# F5529LP_node.net
KiCad netlist of a schematic drawn in EAGLE
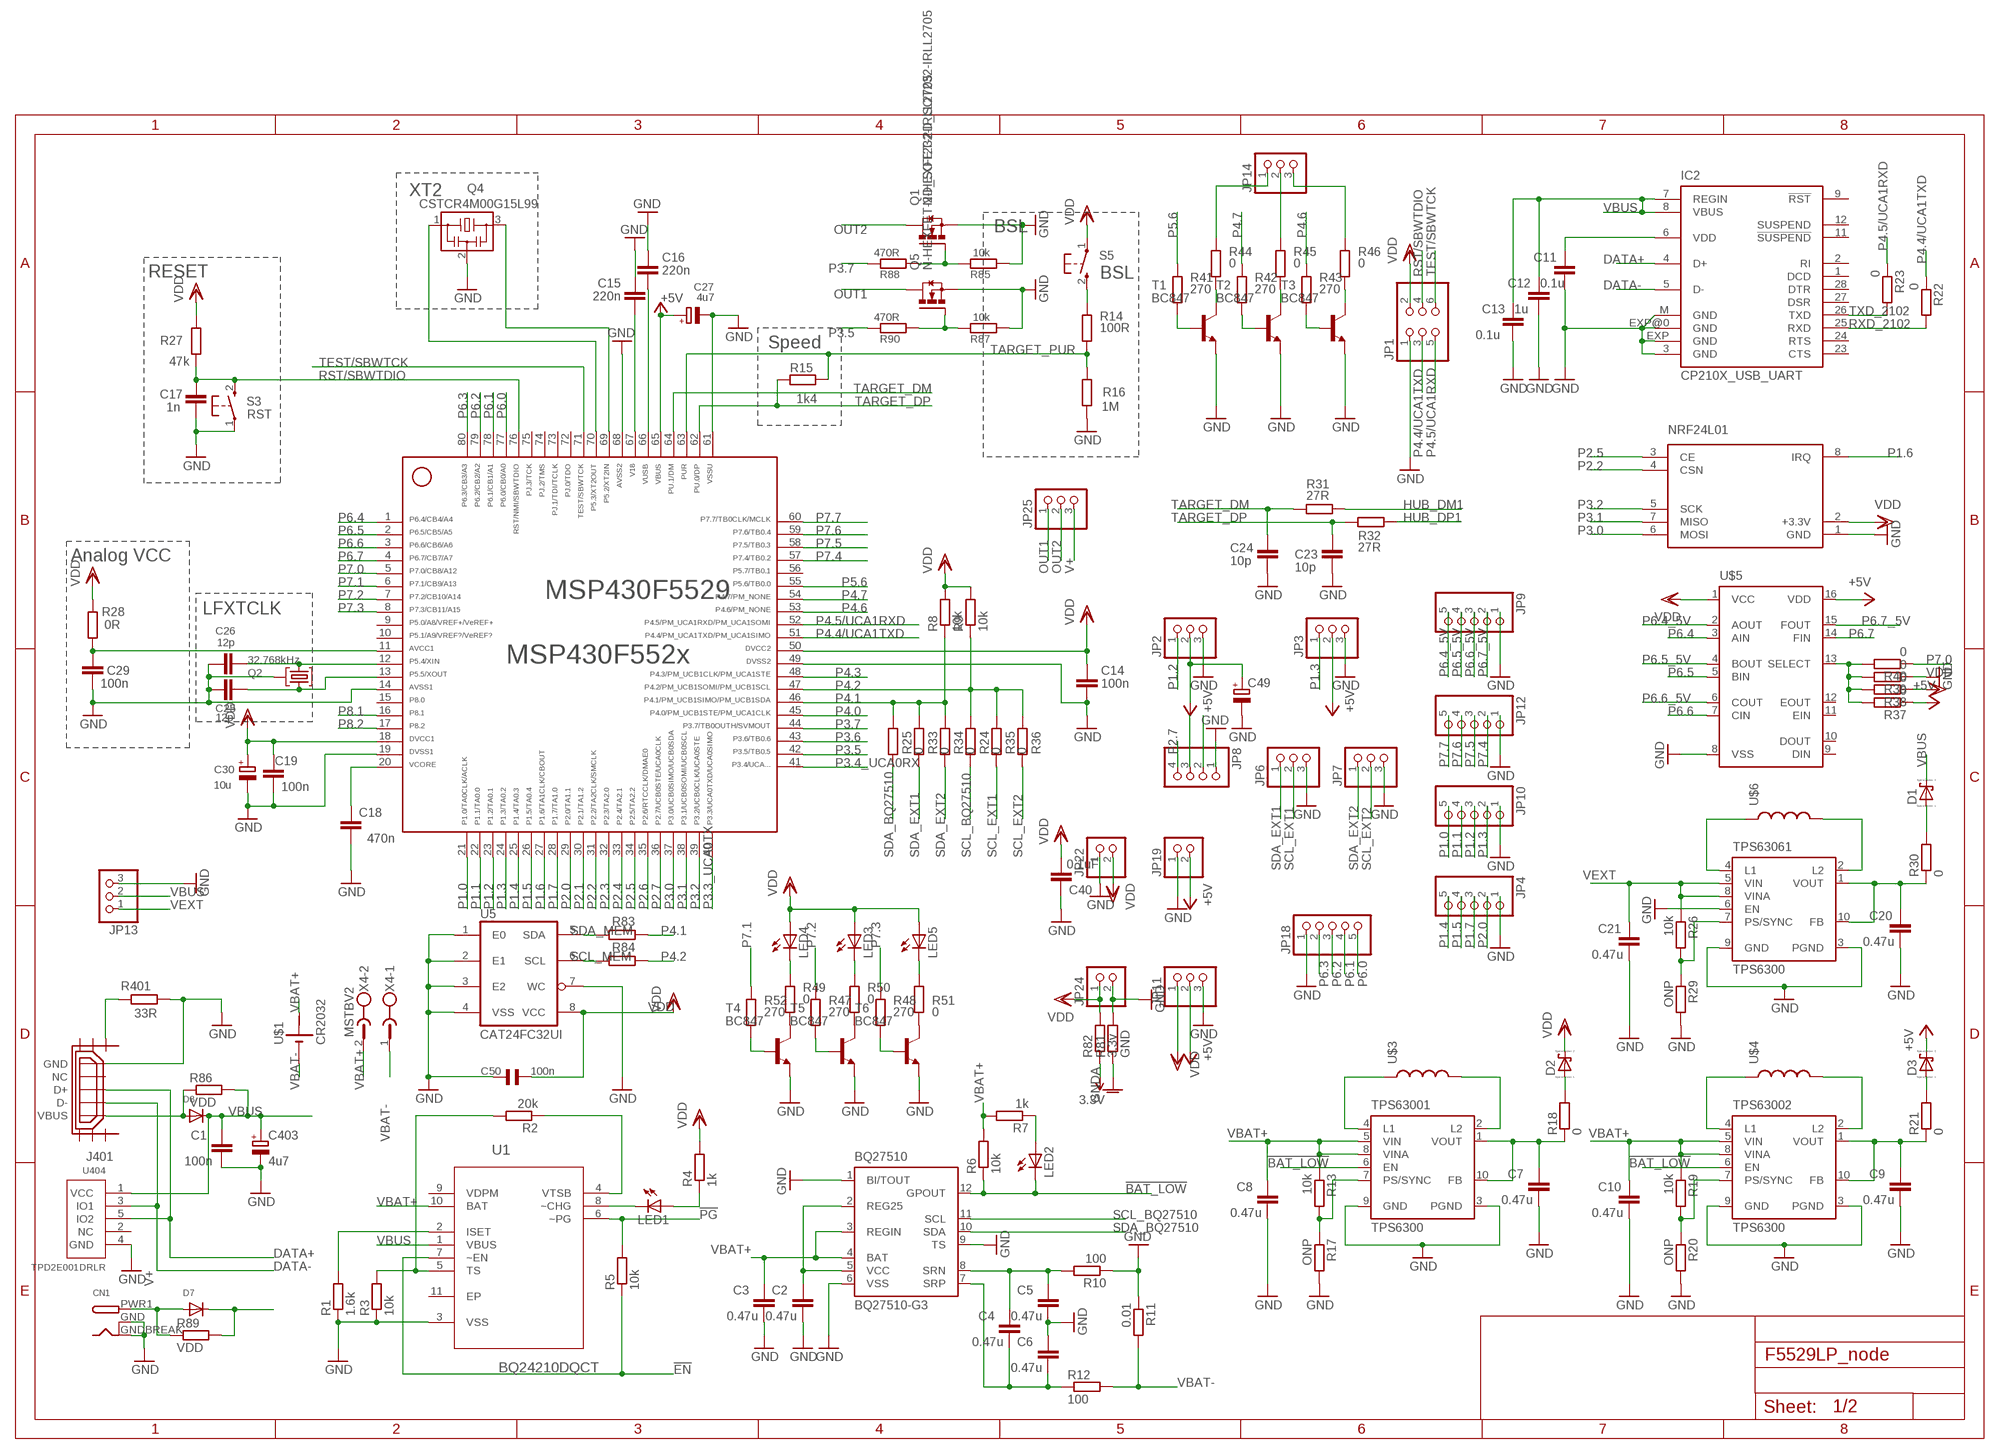
[diagram p0: schematic, sheet 1]
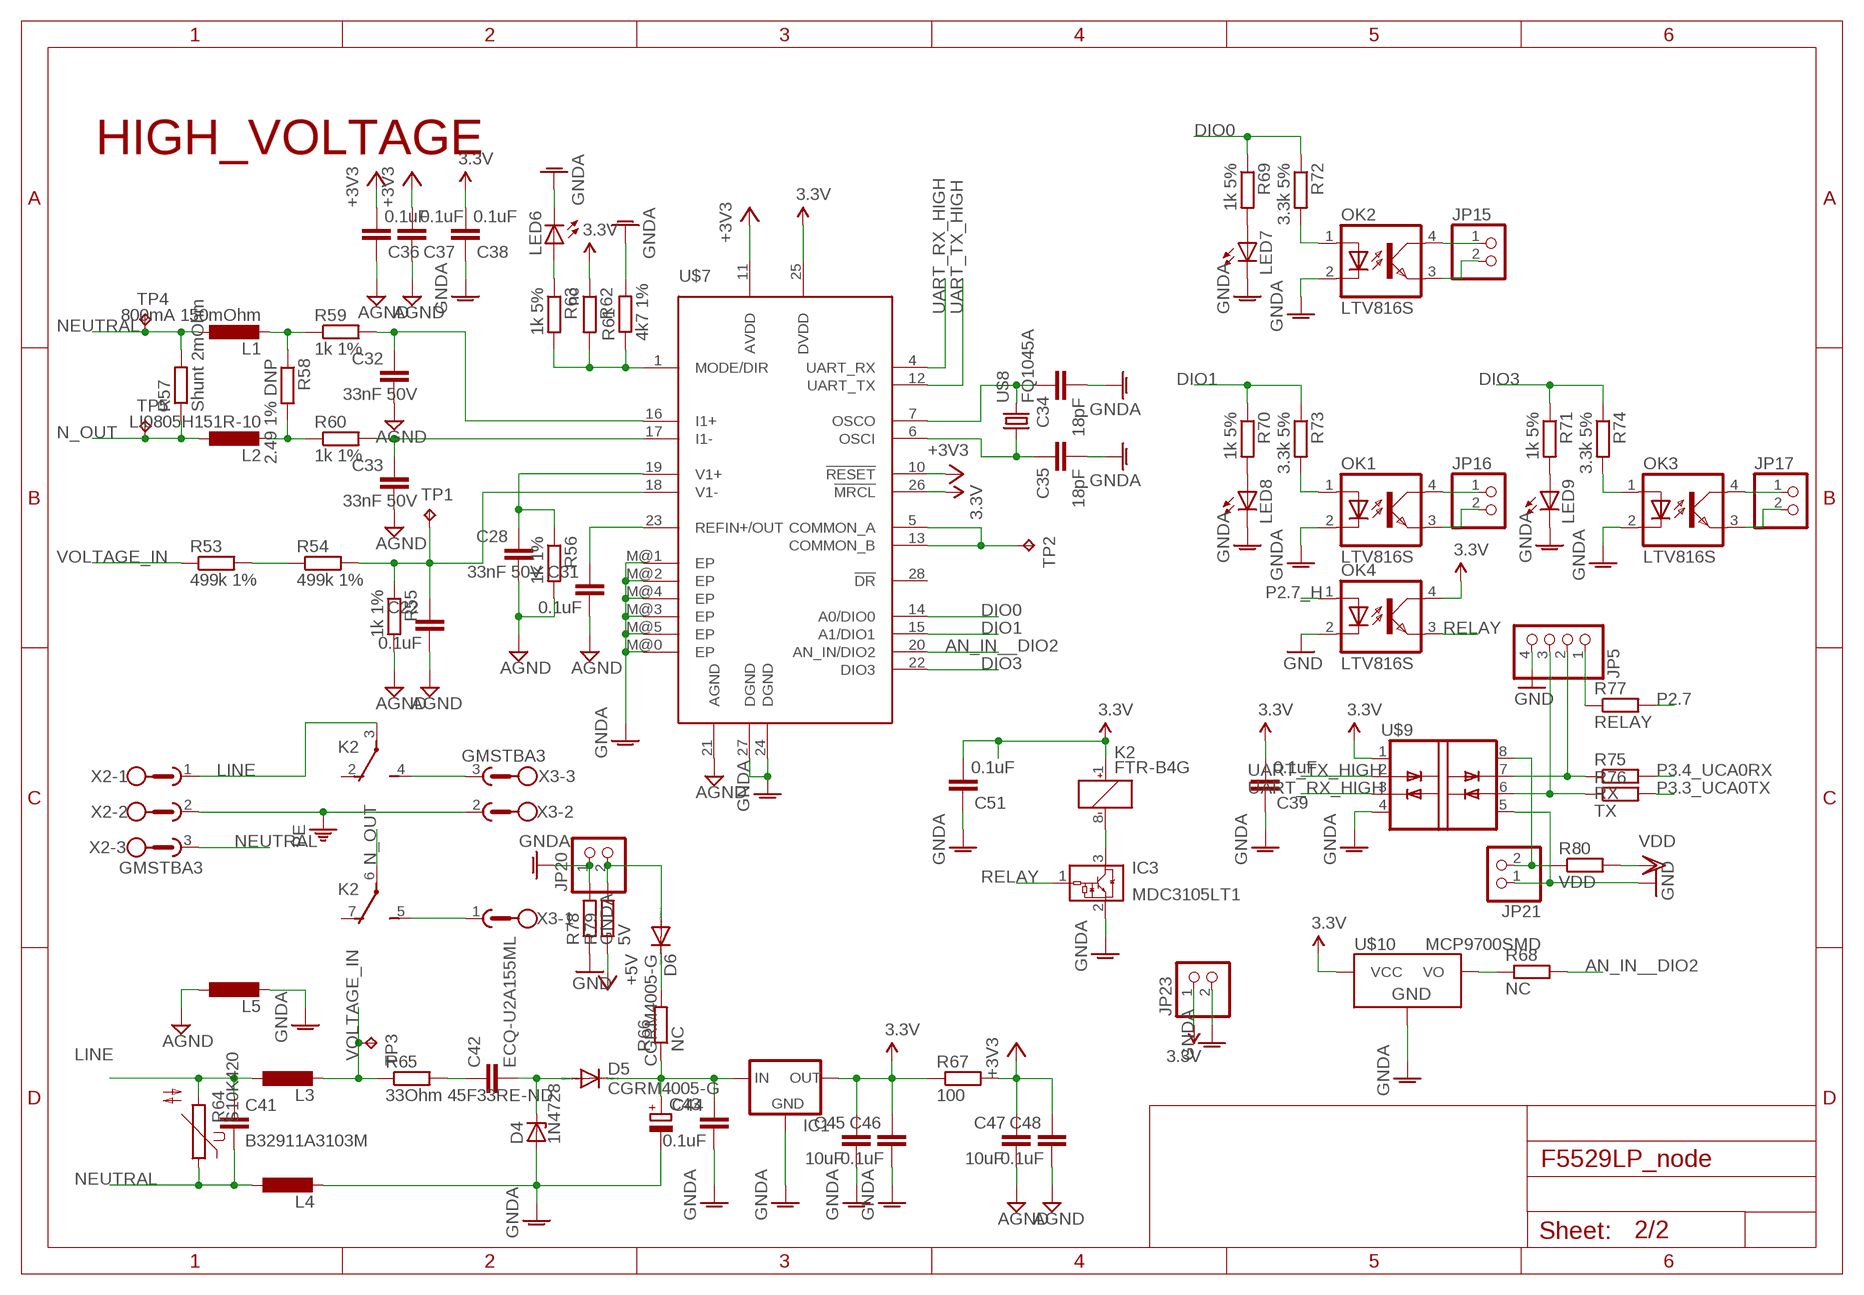
[diagram p1: schematic, sheet 2]

(export (version "E")
  (design (tool "Eeschema 10.0.6"))
  (components
    (comp (ref "BQ27510")
      (value "BQ27510-G3")
      (footprint "eagle-import:DRZ")
      (libsource (lib "eagle-import") (part "BQ27510-G3"))
    )
    (comp (ref "C1")
      (value "100n")
      (footprint "eagle-import:C0603")
      (libsource (lib "eagle-import") (part "C-EUC0603"))
    )
    (comp (ref "C2")
      (value "0.47u")
      (footprint "eagle-import:C0603")
      (libsource (lib "eagle-import") (part "C-EUC0603"))
    )
    (comp (ref "C3")
      (value "0.47u")
      (footprint "eagle-import:C0603")
      (libsource (lib "eagle-import") (part "C-EUC0603"))
    )
    (comp (ref "C4")
      (value "0.47u")
      (footprint "eagle-import:C0603")
      (libsource (lib "eagle-import") (part "C-EUC0603"))
    )
    (comp (ref "C5")
      (value "0.47u")
      (footprint "eagle-import:C0603")
      (libsource (lib "eagle-import") (part "C-EUC0603"))
    )
    (comp (ref "C6")
      (value "0.47u")
      (footprint "eagle-import:C0603")
      (libsource (lib "eagle-import") (part "C-EUC0603"))
    )
    (comp (ref "C7")
      (value "0.47u")
      (footprint "eagle-import:C0603")
      (libsource (lib "eagle-import") (part "C-EUC0603"))
    )
    (comp (ref "C8")
      (value "0.47u")
      (footprint "eagle-import:C0603")
      (libsource (lib "eagle-import") (part "C-EUC0603"))
    )
    (comp (ref "C9")
      (value "0.47u")
      (footprint "eagle-import:C0603")
      (libsource (lib "eagle-import") (part "C-EUC0603"))
    )
    (comp (ref "C10")
      (value "0.47u")
      (footprint "eagle-import:C0603")
      (libsource (lib "eagle-import") (part "C-EUC0603"))
    )
    (comp (ref "C11")
      (value "0.1u")
      (footprint "eagle-import:C0603")
      (libsource (lib "eagle-import") (part "C-EUC0603"))
    )
    (comp (ref "C12")
      (value "1u")
      (footprint "eagle-import:C0603")
      (libsource (lib "eagle-import") (part "C-EUC0603"))
    )
    (comp (ref "C13")
      (value "0.1u")
      (footprint "eagle-import:C0603")
      (libsource (lib "eagle-import") (part "C-EUC0603"))
    )
    (comp (ref "C14")
      (value "100n")
      (footprint "eagle-import:C0603")
      (libsource (lib "eagle-import") (part "C-EUC0603"))
    )
    (comp (ref "C15")
      (value "220n")
      (footprint "eagle-import:C0603")
      (libsource (lib "eagle-import") (part "C-EUC0603"))
    )
    (comp (ref "C16")
      (value "220n")
      (footprint "eagle-import:C0603")
      (libsource (lib "eagle-import") (part "C-EUC0603"))
    )
    (comp (ref "C17")
      (value "1n")
      (footprint "eagle-import:C0603")
      (libsource (lib "eagle-import") (part "C-EUC0603"))
    )
    (comp (ref "C18")
      (value "470n")
      (footprint "eagle-import:C0603")
      (libsource (lib "eagle-import") (part "C-EUC0603"))
    )
    (comp (ref "C19")
      (value "100n")
      (footprint "eagle-import:C0603")
      (libsource (lib "eagle-import") (part "C-EUC0603"))
    )
    (comp (ref "C20")
      (value "0.47u")
      (footprint "eagle-import:C0603")
      (libsource (lib "eagle-import") (part "C-EUC0603"))
    )
    (comp (ref "C21")
      (value "0.47u")
      (footprint "eagle-import:C0603")
      (libsource (lib "eagle-import") (part "C-EUC0603"))
    )
    (comp (ref "C23")
      (value "10p")
      (footprint "eagle-import:C0603")
      (libsource (lib "eagle-import") (part "C-EUC0603"))
    )
    (comp (ref "C24")
      (value "10p")
      (footprint "eagle-import:C0603")
      (libsource (lib "eagle-import") (part "C-EUC0603"))
    )
    (comp (ref "C25")
      (value "12p")
      (footprint "eagle-import:C0603")
      (libsource (lib "eagle-import") (part "C-EUC0603"))
    )
    (comp (ref "C26")
      (value "12p")
      (footprint "eagle-import:C0603")
      (libsource (lib "eagle-import") (part "C-EUC0603"))
    )
    (comp (ref "C27")
      (value "4u7")
      (footprint "eagle-import:A_3216-18R")
      (libsource (lib "eagle-import") (part "CPOL-EUA/3216-18R"))
    )
    (comp (ref "C29")
      (value "100n")
      (footprint "eagle-import:C0603")
      (libsource (lib "eagle-import") (part "C-EUC0603"))
    )
    (comp (ref "C30")
      (value "10u")
      (footprint "eagle-import:A_3216-18R")
      (libsource (lib "eagle-import") (part "CPOL-EUA/3216-18R"))
    )
    (comp (ref "C40")
      (value "0.1uF")
      (footprint "eagle-import:C0603")
      (libsource (lib "eagle-import") (part "C-EUC0603"))
    )
    (comp (ref "C49")
      (value "CPOL-EUF")
      (footprint "eagle-import:PANASONIC_F")
      (libsource (lib "eagle-import") (part "resistor_CPOL-EUF"))
    )
    (comp (ref "C50")
      (value "100n")
      (footprint "eagle-import:0402")
      (libsource (lib "eagle-import") (part "C_SMD0402"))
    )
    (comp (ref "C403")
      (value "4u7")
      (footprint "eagle-import:A_3216-18R")
      (libsource (lib "eagle-import") (part "CPOL-EUA/3216-18R"))
    )
    (comp (ref "CN1")
      (value "DCBARRELSMT")
      (footprint "eagle-import:DCJACK_2MM_SMT")
      (libsource (lib "eagle-import") (part "DCBARRELSMT"))
    )
    (comp (ref "D1")
      (value "SCHOTTKY-DIODE")
      (footprint "eagle-import:DIODE_SMB")
      (libsource (lib "eagle-import") (part "SCHOTTKY-DIODE"))
    )
    (comp (ref "D2")
      (value "SCHOTTKY-DIODE")
      (footprint "eagle-import:DIODE_SMB")
      (libsource (lib "eagle-import") (part "SCHOTTKY-DIODE"))
    )
    (comp (ref "D3")
      (value "SCHOTTKY-DIODE")
      (footprint "eagle-import:DIODE_SMB")
      (libsource (lib "eagle-import") (part "SCHOTTKY-DIODE"))
    )
    (comp (ref "D7")
      (value "DIODESOT23_REFLOW")
      (footprint "eagle-import:SOT23-R")
      (libsource (lib "eagle-import") (part "DIODESOT23_REFLOW"))
    )
    (comp (ref "D8")
      (value "DIODESOT23_REFLOW")
      (footprint "eagle-import:SOT23-R")
      (libsource (lib "eagle-import") (part "DIODESOT23_REFLOW"))
    )
    (comp (ref "IC2")
      (value "CP210X_USB_UART")
      (footprint "eagle-import:MLP28")
      (libsource (lib "eagle-import") (part "CP210X_USB_UART"))
    )
    (comp (ref "J401")
      (value "USB_MICRO_FLIPPED")
      (footprint "eagle-import:HIROSE-ZX62R-B-5P")
      (libsource (lib "eagle-import") (part "USB_MICRO_FLIPPED"))
    )
    (comp (ref "JP1")
      (value "PINHD-2X3")
      (footprint "eagle-import:2X03")
      (libsource (lib "eagle-import") (part "PINHD-2X3"))
    )
    (comp (ref "JP2")
      (value "PINHD-1X3")
      (footprint "eagle-import:1X03")
      (libsource (lib "eagle-import") (part "PINHD-1X3"))
    )
    (comp (ref "JP3")
      (value "PINHD-1X3")
      (footprint "eagle-import:1X03")
      (libsource (lib "eagle-import") (part "PINHD-1X3"))
    )
    (comp (ref "JP4")
      (value "PINHD-1X5_2.00")
      (footprint "eagle-import:1X05M")
      (libsource (lib "eagle-import") (part "PINHD-1X5_2.00"))
    )
    (comp (ref "JP6")
      (value "PINHD-1X3_2.00")
      (footprint "eagle-import:1X03M")
      (libsource (lib "eagle-import") (part "PINHD-1X3_2.00"))
    )
    (comp (ref "JP7")
      (value "PINHD-1X3_2.00")
      (footprint "eagle-import:1X03M")
      (libsource (lib "eagle-import") (part "PINHD-1X3_2.00"))
    )
    (comp (ref "JP8")
      (value "PINHD-1X4_2.00")
      (footprint "eagle-import:1X04M")
      (libsource (lib "eagle-import") (part "PINHD-1X4_2.00"))
    )
    (comp (ref "JP9")
      (value "PINHD-1X5_2.00")
      (footprint "eagle-import:1X05M")
      (libsource (lib "eagle-import") (part "PINHD-1X5_2.00"))
    )
    (comp (ref "JP10")
      (value "PINHD-1X5_2.00")
      (footprint "eagle-import:1X05M")
      (libsource (lib "eagle-import") (part "PINHD-1X5_2.00"))
    )
    (comp (ref "JP11")
      (value "PINHD-1X3_2.00")
      (footprint "eagle-import:1X03M")
      (libsource (lib "eagle-import") (part "PINHD-1X3_2.00"))
    )
    (comp (ref "JP12")
      (value "PINHD-1X5_2.00")
      (footprint "eagle-import:1X05M")
      (libsource (lib "eagle-import") (part "PINHD-1X5_2.00"))
    )
    (comp (ref "JP13")
      (value "PINHD-1X3_2.00")
      (footprint "eagle-import:1X03M")
      (libsource (lib "eagle-import") (part "PINHD-1X3_2.00"))
    )
    (comp (ref "JP14")
      (value "PINHD-1X3_2.00")
      (footprint "eagle-import:1X03M")
      (libsource (lib "eagle-import") (part "PINHD-1X3_2.00"))
    )
    (comp (ref "JP18")
      (value "PINHD-1X5_2.00")
      (footprint "eagle-import:1X05M")
      (libsource (lib "eagle-import") (part "PINHD-1X5_2.00"))
    )
    (comp (ref "JP19")
      (value "PINHD-1X2_2.00")
      (footprint "eagle-import:1X02M")
      (libsource (lib "eagle-import") (part "PINHD-1X2_2.00"))
    )
    (comp (ref "JP22")
      (value "PINHD-1X2_2.00")
      (footprint "eagle-import:1X02M")
      (libsource (lib "eagle-import") (part "PINHD-1X2_2.00"))
    )
    (comp (ref "JP24")
      (value "PINHD-1X2_2.00")
      (footprint "eagle-import:1X02M")
      (libsource (lib "eagle-import") (part "PINHD-1X2_2.00"))
    )
    (comp (ref "JP25")
      (value "PINHD-1X3")
      (footprint "eagle-import:1X03")
      (libsource (lib "eagle-import") (part "PINHD-1X3"))
    )
    (comp (ref "LED1")
      (value "LEDSML0805")
      (footprint "eagle-import:SML0805")
      (libsource (lib "eagle-import") (part "LEDSML0805"))
    )
    (comp (ref "LED2")
      (value "LEDSML0805")
      (footprint "eagle-import:SML0805")
      (libsource (lib "eagle-import") (part "LEDSML0805"))
    )
    (comp (ref "LED3")
      (value "LEDSML0805")
      (footprint "eagle-import:SML0805")
      (libsource (lib "eagle-import") (part "LEDSML0805"))
    )
    (comp (ref "LED4")
      (value "LEDSML0805")
      (footprint "eagle-import:SML0805")
      (libsource (lib "eagle-import") (part "LEDSML0805"))
    )
    (comp (ref "LED5")
      (value "LEDSML0805")
      (footprint "eagle-import:SML0805")
      (libsource (lib "eagle-import") (part "LEDSML0805"))
    )
    (comp (ref "MSP430F5529")
      (value "MSP430F5529IPNR")
      (footprint "eagle-import:PN80")
      (libsource (lib "eagle-import") (part "F552X---PN80"))
    )
    (comp (ref "NRF24L01")
      (value "NRF24L01HP")
      (footprint "eagle-import:NRF24L01_HP")
      (libsource (lib "eagle-import") (part "NRF24L01HP"))
    )
    (comp (ref "Q1")
      (value "N-HEXFET-2D_SOT232-IRLL2705")
      (footprint "eagle-import:SOT223")
      (libsource (lib "eagle-import") (part "N-HEXFET-2D_?-SOT232IRLL2705"))
    )
    (comp (ref "Q2")
      (value "32.768kHz")
      (footprint "eagle-import:MS3V-T1R")
      (libsource (lib "eagle-import") (part "MS3V-T1R"))
    )
    (comp (ref "Q4")
      (value "CSTCR4M00G15L99")
      (footprint "eagle-import:MURATA-FILTER_CSTCR")
      (fields (field (name "MPN") "CSTCR6M00G53-R0"))
      (libsource (lib "eagle-import") (part "MURATA-FILTER_CSTCR6M00G53Z"))
    )
    (comp (ref "Q5")
      (value "N-HEXFET-2D_SOT232-IRLL2705")
      (footprint "eagle-import:SOT223")
      (libsource (lib "eagle-import") (part "N-HEXFET-2D_?-SOT232IRLL2705"))
    )
    (comp (ref "R1")
      (value "1.6k")
      (footprint "eagle-import:R0603")
      (libsource (lib "eagle-import") (part "resistor_R-EU_R0603"))
    )
    (comp (ref "R2")
      (value "20k")
      (footprint "eagle-import:R0603")
      (libsource (lib "eagle-import") (part "resistor_R-EU_R0603"))
    )
    (comp (ref "R3")
      (value "10k")
      (footprint "eagle-import:R0603")
      (libsource (lib "eagle-import") (part "resistor_R-EU_R0603"))
    )
    (comp (ref "R4")
      (value "1k")
      (footprint "eagle-import:R0603")
      (libsource (lib "eagle-import") (part "resistor_R-EU_R0603"))
    )
    (comp (ref "R5")
      (value "10k")
      (footprint "eagle-import:R0603")
      (libsource (lib "eagle-import") (part "resistor_R-EU_R0603"))
    )
    (comp (ref "R6")
      (value "10k")
      (footprint "eagle-import:R0603")
      (libsource (lib "eagle-import") (part "resistor_R-EU_R0603"))
    )
    (comp (ref "R7")
      (value "1k")
      (footprint "eagle-import:R0603")
      (libsource (lib "eagle-import") (part "resistor_R-EU_R0603"))
    )
    (comp (ref "R8")
      (value "10k")
      (footprint "eagle-import:R0603")
      (libsource (lib "eagle-import") (part "resistor_R-EU_R0603"))
    )
    (comp (ref "R9")
      (value "10k")
      (footprint "eagle-import:R0603")
      (libsource (lib "eagle-import") (part "resistor_R-EU_R0603"))
    )
    (comp (ref "R10")
      (value "100")
      (footprint "eagle-import:R0603")
      (libsource (lib "eagle-import") (part "resistor_R-EU_R0603"))
    )
    (comp (ref "R11")
      (value "0.01")
      (footprint "eagle-import:R0603")
      (libsource (lib "eagle-import") (part "resistor_R-EU_R0603"))
    )
    (comp (ref "R12")
      (value "100")
      (footprint "eagle-import:R0603")
      (libsource (lib "eagle-import") (part "resistor_R-EU_R0603"))
    )
    (comp (ref "R13")
      (value "10k")
      (footprint "eagle-import:R0603")
      (libsource (lib "eagle-import") (part "resistor_R-EU_R0603"))
    )
    (comp (ref "R14")
      (value "100R")
      (footprint "eagle-import:R0603")
      (libsource (lib "eagle-import") (part "R-EU_R0603"))
    )
    (comp (ref "R15")
      (value "1k4")
      (footprint "eagle-import:R0603")
      (libsource (lib "eagle-import") (part "R-EU_R0603"))
    )
    (comp (ref "R16")
      (value "1M")
      (footprint "eagle-import:R0603")
      (libsource (lib "eagle-import") (part "R-EU_R0603"))
    )
    (comp (ref "R17")
      (value "ONP")
      (footprint "eagle-import:R0603")
      (libsource (lib "eagle-import") (part "resistor_R-EU_R0603"))
    )
    (comp (ref "R18")
      (value "0")
      (footprint "eagle-import:R0603")
      (libsource (lib "eagle-import") (part "resistor_R-EU_R0603"))
    )
    (comp (ref "R19")
      (value "10k")
      (footprint "eagle-import:R0603")
      (libsource (lib "eagle-import") (part "resistor_R-EU_R0603"))
    )
    (comp (ref "R20")
      (value "ONP")
      (footprint "eagle-import:R0603")
      (libsource (lib "eagle-import") (part "resistor_R-EU_R0603"))
    )
    (comp (ref "R21")
      (value "0")
      (footprint "eagle-import:R0603")
      (libsource (lib "eagle-import") (part "resistor_R-EU_R0603"))
    )
    (comp (ref "R22")
      (value "0")
      (footprint "eagle-import:R0603")
      (libsource (lib "eagle-import") (part "resistor_R-EU_R0603"))
    )
    (comp (ref "R23")
      (value "0")
      (footprint "eagle-import:R0603")
      (libsource (lib "eagle-import") (part "resistor_R-EU_R0603"))
    )
    (comp (ref "R24")
      (value "0")
      (footprint "eagle-import:R0201")
      (libsource (lib "eagle-import") (part "R-EU_R0201"))
    )
    (comp (ref "R25")
      (value "0")
      (footprint "eagle-import:R0201")
      (libsource (lib "eagle-import") (part "R-EU_R0201"))
    )
    (comp (ref "R26")
      (value "10k")
      (footprint "eagle-import:R0603")
      (libsource (lib "eagle-import") (part "resistor_R-EU_R0603"))
    )
    (comp (ref "R27")
      (value "47k")
      (footprint "eagle-import:R0603")
      (libsource (lib "eagle-import") (part "R-EU_R0603"))
    )
    (comp (ref "R28")
      (value "0R")
      (footprint "eagle-import:R0603")
      (libsource (lib "eagle-import") (part "R-EU_R0603"))
    )
    (comp (ref "R29")
      (value "ONP")
      (footprint "eagle-import:R0603")
      (libsource (lib "eagle-import") (part "resistor_R-EU_R0603"))
    )
    (comp (ref "R30")
      (value "0")
      (footprint "eagle-import:R0603")
      (libsource (lib "eagle-import") (part "resistor_R-EU_R0603"))
    )
    (comp (ref "R31")
      (value "27R")
      (footprint "eagle-import:R0603")
      (libsource (lib "eagle-import") (part "R-EU_R0603"))
    )
    (comp (ref "R32")
      (value "27R")
      (footprint "eagle-import:R0603")
      (libsource (lib "eagle-import") (part "R-EU_R0603"))
    )
    (comp (ref "R33")
      (value "0")
      (footprint "eagle-import:R0201")
      (libsource (lib "eagle-import") (part "R-EU_R0201"))
    )
    (comp (ref "R34")
      (value "0")
      (footprint "eagle-import:R0201")
      (libsource (lib "eagle-import") (part "R-EU_R0201"))
    )
    (comp (ref "R35")
      (value "0")
      (footprint "eagle-import:R0201")
      (libsource (lib "eagle-import") (part "R-EU_R0201"))
    )
    (comp (ref "R36")
      (value "0")
      (footprint "eagle-import:R0201")
      (libsource (lib "eagle-import") (part "R-EU_R0201"))
    )
    (comp (ref "R37")
      (value "0")
      (footprint "eagle-import:R0603")
      (libsource (lib "eagle-import") (part "resistor_R-EU_R0603"))
    )
    (comp (ref "R38")
      (value "0")
      (footprint "eagle-import:R0603")
      (libsource (lib "eagle-import") (part "resistor_R-EU_R0603"))
    )
    (comp (ref "R39")
      (value "0")
      (footprint "eagle-import:R0603")
      (libsource (lib "eagle-import") (part "resistor_R-EU_R0603"))
    )
    (comp (ref "R40")
      (value "0")
      (footprint "eagle-import:R0603")
      (libsource (lib "eagle-import") (part "resistor_R-EU_R0603"))
    )
    (comp (ref "R41")
      (value "270")
      (footprint "eagle-import:R0603")
      (libsource (lib "eagle-import") (part "R-EU_R0603"))
    )
    (comp (ref "R42")
      (value "270")
      (footprint "eagle-import:R0603")
      (libsource (lib "eagle-import") (part "R-EU_R0603"))
    )
    (comp (ref "R43")
      (value "270")
      (footprint "eagle-import:R0603")
      (libsource (lib "eagle-import") (part "R-EU_R0603"))
    )
    (comp (ref "R44")
      (value "0")
      (footprint "eagle-import:R0603")
      (libsource (lib "eagle-import") (part "R-EU_R0603"))
    )
    (comp (ref "R45")
      (value "0")
      (footprint "eagle-import:R0603")
      (libsource (lib "eagle-import") (part "R-EU_R0603"))
    )
    (comp (ref "R46")
      (value "0")
      (footprint "eagle-import:R0603")
      (libsource (lib "eagle-import") (part "R-EU_R0603"))
    )
    (comp (ref "R47")
      (value "270")
      (footprint "eagle-import:R0603")
      (libsource (lib "eagle-import") (part "R-EU_R0603"))
    )
    (comp (ref "R48")
      (value "270")
      (footprint "eagle-import:R0603")
      (libsource (lib "eagle-import") (part "R-EU_R0603"))
    )
    (comp (ref "R49")
      (value "0")
      (footprint "eagle-import:R0603")
      (libsource (lib "eagle-import") (part "R-EU_R0603"))
    )
    (comp (ref "R50")
      (value "0")
      (footprint "eagle-import:R0603")
      (libsource (lib "eagle-import") (part "R-EU_R0603"))
    )
    (comp (ref "R51")
      (value "0")
      (footprint "eagle-import:R0603")
      (libsource (lib "eagle-import") (part "R-EU_R0603"))
    )
    (comp (ref "R52")
      (value "270")
      (footprint "eagle-import:R0603")
      (libsource (lib "eagle-import") (part "R-EU_R0603"))
    )
    (comp (ref "R81")
      (value "GND")
      (footprint "eagle-import:R0402")
      (libsource (lib "eagle-import") (part "resistor_R-EU_R0402"))
    )
    (comp (ref "R82")
      (value "3.3v")
      (footprint "eagle-import:R0402")
      (libsource (lib "eagle-import") (part "resistor_R-EU_R0402"))
    )
    (comp (ref "R83")
      (value "0")
      (footprint "eagle-import:R0201")
      (libsource (lib "eagle-import") (part "R-EU_R0201"))
    )
    (comp (ref "R84")
      (value "0")
      (footprint "eagle-import:R0201")
      (libsource (lib "eagle-import") (part "R-EU_R0201"))
    )
    (comp (ref "R85")
      (value "10k")
      (footprint "eagle-import:0603")
      (libsource (lib "eagle-import") (part "R_SMDR0603"))
    )
    (comp (ref "R86")
      (value "VDD")
      (footprint "eagle-import:R0201")
      (libsource (lib "eagle-import") (part "resistor_R-EU_R0201"))
    )
    (comp (ref "R87")
      (value "10k")
      (footprint "eagle-import:0603")
      (libsource (lib "eagle-import") (part "R_SMDR0603"))
    )
    (comp (ref "R88")
      (value "470R")
      (footprint "eagle-import:0603")
      (libsource (lib "eagle-import") (part "R_SMDR0603"))
    )
    (comp (ref "R89")
      (value "VDD")
      (footprint "eagle-import:R0201")
      (libsource (lib "eagle-import") (part "resistor_R-EU_R0201"))
    )
    (comp (ref "R90")
      (value "470R")
      (footprint "eagle-import:0603")
      (libsource (lib "eagle-import") (part "R_SMDR0603"))
    )
    (comp (ref "R401")
      (value "33R")
      (footprint "eagle-import:R0603")
      (libsource (lib "eagle-import") (part "R-EU_R0603"))
    )
    (comp (ref "S3")
      (value "RST")
      (footprint "eagle-import:PBTH")
      (libsource (lib "eagle-import") (part "PB"))
    )
    (comp (ref "S5")
      (value "BSL")
      (footprint "eagle-import:PBTH")
      (libsource (lib "eagle-import") (part "PB"))
    )
    (comp (ref "T1")
      (value "BC847")
      (footprint "eagle-import:SOT23")
      (libsource (lib "eagle-import") (part "BC847"))
    )
    (comp (ref "T2")
      (value "BC847")
      (footprint "eagle-import:SOT23")
      (libsource (lib "eagle-import") (part "BC847"))
    )
    (comp (ref "T3")
      (value "BC847")
      (footprint "eagle-import:SOT23")
      (libsource (lib "eagle-import") (part "BC847"))
    )
    (comp (ref "T4")
      (value "BC847")
      (footprint "eagle-import:SOT23")
      (libsource (lib "eagle-import") (part "BC847"))
    )
    (comp (ref "T5")
      (value "BC847")
      (footprint "eagle-import:SOT23")
      (libsource (lib "eagle-import") (part "BC847"))
    )
    (comp (ref "T6")
      (value "BC847")
      (footprint "eagle-import:SOT23")
      (libsource (lib "eagle-import") (part "BC847"))
    )
    (comp (ref "TPS63001")
      (value "TPS6300")
      (footprint "eagle-import:DRC-S-PVSON-N10")
      (fields (field (name "MPN") "TPS63000DRCTG4"))
      (libsource (lib "eagle-import") (part "TPS6300"))
    )
    (comp (ref "TPS63002")
      (value "TPS6300")
      (footprint "eagle-import:DRC-S-PVSON-N10")
      (fields (field (name "MPN") "TPS63000DRCTG4"))
      (libsource (lib "eagle-import") (part "TPS6300"))
    )
    (comp (ref "TPS63061")
      (value "TPS6300")
      (footprint "eagle-import:DRC-S-PVSON-N10")
      (fields (field (name "MPN") "TPS63000DRCTG4"))
      (libsource (lib "eagle-import") (part "TPS6300"))
    )
    (comp (ref "U$1")
      (value "CR2032")
      (footprint "eagle-import:CR2032")
      (libsource (lib "eagle-import") (part "CR2032"))
    )
    (comp (ref "U$3")
      (value "INDUCTOR-B82462G")
      (footprint "eagle-import:B82462G")
      (libsource (lib "eagle-import") (part "INDUCTOR-B82462G"))
    )
    (comp (ref "U$4")
      (value "INDUCTOR-B82462G")
      (footprint "eagle-import:B82462G")
      (libsource (lib "eagle-import") (part "INDUCTOR-B82462G"))
    )
    (comp (ref "U$5")
      (value "CD4504B")
      (footprint "eagle-import:SOIC16")
      (libsource (lib "eagle-import") (part "CD4504B"))
    )
    (comp (ref "U$6")
      (value "INDUCTOR-B82462G")
      (footprint "eagle-import:B82462G")
      (libsource (lib "eagle-import") (part "INDUCTOR-B82462G"))
    )
    (comp (ref "U1")
      (value "BQ24210DQCT")
      (footprint "eagle-import:SON50P200X300X80-11N")
      (libsource (lib "eagle-import") (part "BQ24210DQCT"))
    )
    (comp (ref "U5")
      (value "CAT24FC32UI")
      (footprint "eagle-import:TSSOP8")
      (libsource (lib "eagle-import") (part "M24XXX"))
    )
    (comp (ref "U404")
      (value "TPD2E001DRLR")
      (footprint "eagle-import:TPD2E001-DRL")
      (libsource (lib "eagle-import") (part "TPD2E001"))
    )
    (comp (ref "X4")
      (value "MSTBV2")
      (footprint "eagle-import:MSTBV2")
      (fields (field (name "MPN") "MSTBV 2,5/2-GF-5.08"))
      (libsource (lib "eagle-import") (part "MSTBV2"))
    )
    (comp (ref "C22")
      (value "0.1uF")
      (footprint "eagle-import:C0603")
      (libsource (lib "eagle-import") (part "C-EUC0603"))
    )
    (comp (ref "C28")
      (value "33nF 50V")
      (footprint "eagle-import:C0603")
      (libsource (lib "eagle-import") (part "C-EUC0603"))
    )
    (comp (ref "C31")
      (value "0.1uF")
      (footprint "eagle-import:C0603")
      (libsource (lib "eagle-import") (part "C-EUC0603"))
    )
    (comp (ref "C32")
      (value "33nF 50V")
      (footprint "eagle-import:C0603")
      (libsource (lib "eagle-import") (part "C-EUC0603"))
    )
    (comp (ref "C33")
      (value "33nF 50V")
      (footprint "eagle-import:C0603")
      (libsource (lib "eagle-import") (part "C-EUC0603"))
    )
    (comp (ref "C34")
      (value "18pF")
      (footprint "eagle-import:C0603")
      (libsource (lib "eagle-import") (part "C-EUC0603"))
    )
    (comp (ref "C35")
      (value "18pF")
      (footprint "eagle-import:C0603")
      (libsource (lib "eagle-import") (part "C-EUC0603"))
    )
    (comp (ref "C36")
      (value "0.1uF")
      (footprint "eagle-import:C0603")
      (libsource (lib "eagle-import") (part "C-EUC0603"))
    )
    (comp (ref "C37")
      (value "0.1uF")
      (footprint "eagle-import:C0603")
      (libsource (lib "eagle-import") (part "C-EUC0603"))
    )
    (comp (ref "C38")
      (value "0.1uF")
      (footprint "eagle-import:C0603")
      (libsource (lib "eagle-import") (part "C-EUC0603"))
    )
    (comp (ref "C39")
      (value "0.1uF")
      (footprint "eagle-import:C0603")
      (libsource (lib "eagle-import") (part "C-EUC0603"))
    )
    (comp (ref "C41")
      (value "B32911A3103M")
      (footprint "eagle-import:C075-042X103")
      (libsource (lib "eagle-import") (part "resistor_C-EU075-042X103"))
    )
    (comp (ref "C42")
      (value "ECQ-U2A155ML")
      (footprint "eagle-import:C275-173X316")
      (libsource (lib "eagle-import") (part "resistor_C-EU275-173X316"))
    )
    (comp (ref "C43")
      (value "CPOL-EUF")
      (footprint "eagle-import:PANASONIC_F")
      (libsource (lib "eagle-import") (part "resistor_CPOL-EUF"))
    )
    (comp (ref "C44")
      (value "0.1uF")
      (footprint "eagle-import:C0603")
      (libsource (lib "eagle-import") (part "C-EUC0603"))
    )
    (comp (ref "C45")
      (value "10uF")
      (footprint "eagle-import:C1206")
      (libsource (lib "eagle-import") (part "C-EUC1206"))
    )
    (comp (ref "C46")
      (value "0.1uF")
      (footprint "eagle-import:C0603")
      (libsource (lib "eagle-import") (part "C-EUC0603"))
    )
    (comp (ref "C47")
      (value "10uF")
      (footprint "eagle-import:C1206")
      (libsource (lib "eagle-import") (part "C-EUC1206"))
    )
    (comp (ref "C48")
      (value "0.1uF")
      (footprint "eagle-import:C0603")
      (libsource (lib "eagle-import") (part "C-EUC0603"))
    )
    (comp (ref "C51")
      (value "0.1uF")
      (footprint "eagle-import:C0805")
      (libsource (lib "eagle-import") (part "C-EUC0805"))
    )
    (comp (ref "D4")
      (value "1N4728")
      (footprint "eagle-import:DO41Z10")
      (libsource (lib "eagle-import") (part "1N4728"))
    )
    (comp (ref "D5")
      (value "CGRM4005-G")
      (footprint "eagle-import:SOD-123_MINI-SMA")
      (libsource (lib "eagle-import") (part "CGRM400-G5"))
    )
    (comp (ref "D6")
      (value "CGRM4005-G")
      (footprint "eagle-import:SOD-123_MINI-SMA")
      (libsource (lib "eagle-import") (part "CGRM400-G5"))
    )
    (comp (ref "IC1")
      (value "LM1117")
      (footprint "eagle-import:SOT223")
      (libsource (lib "eagle-import") (part "LM1117"))
    )
    (comp (ref "IC3")
      (value "MDC3105LT1")
      (footprint "eagle-import:SOT23")
      (fields (field (name "MF") "ON SEMICONDUCTOR"))
      (libsource (lib "eagle-import") (part "MDC3105LT1"))
    )
    (comp (ref "JP5")
      (value "PINHD-1X4_2.00")
      (footprint "eagle-import:1X04M")
      (libsource (lib "eagle-import") (part "PINHD-1X4_2.00"))
    )
    (comp (ref "JP15")
      (value "PINHD-1X2_2.00")
      (footprint "eagle-import:1X02M")
      (libsource (lib "eagle-import") (part "PINHD-1X2_2.00"))
    )
    (comp (ref "JP16")
      (value "PINHD-1X2_2.00")
      (footprint "eagle-import:1X02M")
      (libsource (lib "eagle-import") (part "PINHD-1X2_2.00"))
    )
    (comp (ref "JP17")
      (value "PINHD-1X2_2.00")
      (footprint "eagle-import:1X02M")
      (libsource (lib "eagle-import") (part "PINHD-1X2_2.00"))
    )
    (comp (ref "JP20")
      (value "PINHD-1X2_2.00")
      (footprint "eagle-import:1X02M")
      (libsource (lib "eagle-import") (part "PINHD-1X2_2.00"))
    )
    (comp (ref "JP21")
      (value "PINHD-1X2_2.00")
      (footprint "eagle-import:1X02M")
      (libsource (lib "eagle-import") (part "PINHD-1X2_2.00"))
    )
    (comp (ref "JP23")
      (value "PINHD-1X2_2.00")
      (footprint "eagle-import:1X02M")
      (libsource (lib "eagle-import") (part "PINHD-1X2_2.00"))
    )
    (comp (ref "K2")
      (value "FTR-B4G")
      (footprint "eagle-import:FTR-B4G")
      (libsource (lib "eagle-import") (part "FTR-B4G"))
    )
    (comp (ref "L1")
      (value "800mA 150mOhm")
      (footprint "eagle-import:L2825P")
      (libsource (lib "eagle-import") (part "L-EUL2825P"))
    )
    (comp (ref "L2")
      (value "LI0805H151R-10")
      (footprint "eagle-import:L2825P")
      (libsource (lib "eagle-import") (part "L-EUL2825P"))
    )
    (comp (ref "L3")
      (value "L-EU0207/5V")
      (footprint "eagle-import:0207_5V")
      (libsource (lib "eagle-import") (part "L-EU0207/5V"))
    )
    (comp (ref "L4")
      (value "L-EU0207/5V")
      (footprint "eagle-import:0207_5V")
      (libsource (lib "eagle-import") (part "L-EU0207/5V"))
    )
    (comp (ref "L5")
      (value "L-EUL2825P")
      (footprint "eagle-import:L2825P")
      (libsource (lib "eagle-import") (part "L-EUL2825P"))
    )
    (comp (ref "LED6")
      (value "LEDCHIPLED_0805")
      (footprint "eagle-import:CHIPLED_0805")
      (libsource (lib "eagle-import") (part "LEDCHIPLED_0805"))
    )
    (comp (ref "LED7")
      (value "LEDCHIPLED_0805")
      (footprint "eagle-import:CHIPLED_0805")
      (libsource (lib "eagle-import") (part "LEDCHIPLED_0805"))
    )
    (comp (ref "LED8")
      (value "LEDCHIPLED_0805")
      (footprint "eagle-import:CHIPLED_0805")
      (libsource (lib "eagle-import") (part "LEDCHIPLED_0805"))
    )
    (comp (ref "LED9")
      (value "LEDCHIPLED_0805")
      (footprint "eagle-import:CHIPLED_0805")
      (libsource (lib "eagle-import") (part "LEDCHIPLED_0805"))
    )
    (comp (ref "OK1")
      (value "LTV816S")
      (footprint "eagle-import:SMD4")
      (libsource (lib "eagle-import") (part "LTV816S"))
    )
    (comp (ref "OK2")
      (value "LTV816S")
      (footprint "eagle-import:SMD4")
      (libsource (lib "eagle-import") (part "LTV816S"))
    )
    (comp (ref "OK3")
      (value "LTV816S")
      (footprint "eagle-import:SMD4")
      (libsource (lib "eagle-import") (part "LTV816S"))
    )
    (comp (ref "OK4")
      (value "LTV816S")
      (footprint "eagle-import:SMD4")
      (libsource (lib "eagle-import") (part "LTV816S"))
    )
    (comp (ref "R53")
      (value "499k 1%")
      (footprint "eagle-import:R2010")
      (libsource (lib "eagle-import") (part "resistor_R-EU_R2010"))
    )
    (comp (ref "R54")
      (value "499k 1%")
      (footprint "eagle-import:R2010")
      (libsource (lib "eagle-import") (part "resistor_R-EU_R2010"))
    )
    (comp (ref "R55")
      (value "1k 1%")
      (footprint "eagle-import:R0603")
      (libsource (lib "eagle-import") (part "resistor_R-EU_R0603"))
    )
    (comp (ref "R56")
      (value "1k 1%")
      (footprint "eagle-import:R0603")
      (libsource (lib "eagle-import") (part "resistor_R-EU_R0603"))
    )
    (comp (ref "R57")
      (value "Shunt 2mOhm")
      (footprint "eagle-import:R2512")
      (libsource (lib "eagle-import") (part "resistor_R-EU_R2512"))
    )
    (comp (ref "R58")
      (value "2.49 1% DNP")
      (footprint "eagle-import:R0603")
      (libsource (lib "eagle-import") (part "resistor_R-EU_R0603"))
    )
    (comp (ref "R59")
      (value "1k 1%")
      (footprint "eagle-import:R0603")
      (libsource (lib "eagle-import") (part "resistor_R-EU_R0603"))
    )
    (comp (ref "R60")
      (value "1k 1%")
      (footprint "eagle-import:R0603")
      (libsource (lib "eagle-import") (part "resistor_R-EU_R0603"))
    )
    (comp (ref "R61")
      (value "4k7 1%")
      (footprint "eagle-import:R0603")
      (libsource (lib "eagle-import") (part "resistor_R-EU_R0603"))
    )
    (comp (ref "R62")
      (value "nc")
      (footprint "eagle-import:R0603")
      (libsource (lib "eagle-import") (part "resistor_R-EU_R0603"))
    )
    (comp (ref "R63")
      (value "1k 5%")
      (footprint "eagle-import:R0603")
      (libsource (lib "eagle-import") (part "resistor_R-EU_R0603"))
    )
    (comp (ref "R64")
      (value "S10K420")
      (footprint "eagle-import:S10K420")
      (libsource (lib "eagle-import") (part "S10K420"))
    )
    (comp (ref "R65")
      (value "33Ohm 45F33RE-ND")
      (footprint "eagle-import:0617V")
      (libsource (lib "eagle-import") (part "resistor_R-EU_0617/5V"))
    )
    (comp (ref "R66")
      (value "NC")
      (footprint "eagle-import:R2010")
      (libsource (lib "eagle-import") (part "resistor_R-EU_R2010"))
    )
    (comp (ref "R67")
      (value "100")
      (footprint "eagle-import:R0603")
      (libsource (lib "eagle-import") (part "resistor_R-EU_R0603"))
    )
    (comp (ref "R68")
      (value "NC")
      (footprint "eagle-import:R0603")
      (libsource (lib "eagle-import") (part "resistor_R-EU_R0603"))
    )
    (comp (ref "R69")
      (value "1k 5%")
      (footprint "eagle-import:R0603")
      (libsource (lib "eagle-import") (part "resistor_R-EU_R0603"))
    )
    (comp (ref "R70")
      (value "1k 5%")
      (footprint "eagle-import:R0603")
      (libsource (lib "eagle-import") (part "resistor_R-EU_R0603"))
    )
    (comp (ref "R71")
      (value "1k 5%")
      (footprint "eagle-import:R0603")
      (libsource (lib "eagle-import") (part "resistor_R-EU_R0603"))
    )
    (comp (ref "R72")
      (value "3.3k 5%")
      (footprint "eagle-import:R0603")
      (libsource (lib "eagle-import") (part "resistor_R-EU_R0603"))
    )
    (comp (ref "R73")
      (value "3.3k 5%")
      (footprint "eagle-import:R0603")
      (libsource (lib "eagle-import") (part "resistor_R-EU_R0603"))
    )
    (comp (ref "R74")
      (value "3.3k 5%")
      (footprint "eagle-import:R0603")
      (libsource (lib "eagle-import") (part "resistor_R-EU_R0603"))
    )
    (comp (ref "R75")
      (value "RX")
      (footprint "eagle-import:R0201")
      (libsource (lib "eagle-import") (part "resistor_R-EU_R0201"))
    )
    (comp (ref "R76")
      (value "TX")
      (footprint "eagle-import:R0201")
      (libsource (lib "eagle-import") (part "resistor_R-EU_R0201"))
    )
    (comp (ref "R77")
      (value "RELAY")
      (footprint "eagle-import:R0201")
      (libsource (lib "eagle-import") (part "resistor_R-EU_R0201"))
    )
    (comp (ref "R78")
      (value "GNDA")
      (footprint "eagle-import:R0402")
      (libsource (lib "eagle-import") (part "resistor_R-EU_R0402"))
    )
    (comp (ref "R79")
      (value "5V")
      (footprint "eagle-import:R0402")
      (libsource (lib "eagle-import") (part "resistor_R-EU_R0402"))
    )
    (comp (ref "R80")
      (value "VDD")
      (footprint "eagle-import:R0201")
      (libsource (lib "eagle-import") (part "resistor_R-EU_R0201"))
    )
    (comp (ref "TP1")
      (value "TPB2,54")
      (footprint "eagle-import:B2,54")
      (libsource (lib "eagle-import") (part "TPB2,54"))
    )
    (comp (ref "TP2")
      (value "TPB1,27")
      (footprint "eagle-import:B1,27")
      (libsource (lib "eagle-import") (part "TPB1,27"))
    )
    (comp (ref "TP3")
      (value "TPB2,54")
      (footprint "eagle-import:B2,54")
      (libsource (lib "eagle-import") (part "TPB2,54"))
    )
    (comp (ref "TP4")
      (value "TPB2,54")
      (footprint "eagle-import:B2,54")
      (libsource (lib "eagle-import") (part "TPB2,54"))
    )
    (comp (ref "TP5")
      (value "TPB2,54")
      (footprint "eagle-import:B2,54")
      (libsource (lib "eagle-import") (part "TPB2,54"))
    )
    (comp (ref "U$7")
      (value "MCP39F501")
      (footprint "eagle-import:QFN28")
      (libsource (lib "eagle-import") (part "MCP39F501"))
    )
    (comp (ref "U$8")
      (value "FQ1045A")
      (footprint "eagle-import:FQ1045A")
      (libsource (lib "eagle-import") (part "FQ1045A"))
    )
    (comp (ref "U$9")
      (value "IL712")
      (footprint "eagle-import:SOIC08")
      (libsource (lib "eagle-import") (part "IL712"))
    )
    (comp (ref "U$10")
      (value "MCP9700SMD")
      (footprint "eagle-import:SOT23-3")
      (libsource (lib "eagle-import") (part "MCP9700SMD"))
    )
    (comp (ref "U$11")
      (value "HIGH_VOLTAGE")
      (footprint "eagle-import:HIGH_VOLTAGE")
      (libsource (lib "eagle-import") (part "HIGH_VOLTAGE"))
    )
    (comp (ref "X2")
      (value "GMSTBA3")
      (footprint "eagle-import:GMSTBA3")
      (fields (field (name "MF") "FARNELL") (field (name "MPN") "1757255"))
      (libsource (lib "eagle-import") (part "GMSTBA3"))
    )
    (comp (ref "X3")
      (value "GMSTBA3")
      (footprint "eagle-import:GMSTBA3")
      (fields (field (name "MF") "FARNELL") (field (name "MPN") "1757255"))
      (libsource (lib "eagle-import") (part "GMSTBA3"))
    )
  )
  (nets
    (net (code "1") (name "+3V3") (class "Default")
      (node (ref "C36") (pin "2") (pinfunction "2_2") (pintype "passive"))
      (node (ref "C37") (pin "2") (pinfunction "2_2") (pintype "passive"))
      (node (ref "C47") (pin "1") (pinfunction "1_1") (pintype "passive"))
      (node (ref "C48") (pin "1") (pinfunction "1_1") (pintype "passive"))
      (node (ref "R67") (pin "2") (pinfunction "2_2") (pintype "passive"))
      (node (ref "U$7") (pin "10") (pinfunction "~{RESET}_10") (pintype "power_in"))
      (node (ref "U$7") (pin "11") (pinfunction "AVDD_11") (pintype "bidirectional"))
    )
    (net (code "2") (name "+5V") (class "Default")
      (node (ref "C27") (pin "+") (pinfunction "+_+") (pintype "passive"))
      (node (ref "C49") (pin "+") (pinfunction "+_+") (pintype "passive"))
      (node (ref "D3") (pin "C") (pinfunction "A_C") (pintype "passive"))
      (node (ref "JP11") (pin "2") (pinfunction "2_2") (pintype "passive"))
      (node (ref "JP19") (pin "2") (pinfunction "2_2") (pintype "passive"))
      (node (ref "JP2") (pin "2") (pinfunction "2_2") (pintype "passive"))
      (node (ref "JP3") (pin "2") (pinfunction "2_2") (pintype "passive"))
      (node (ref "MSP430F5529") (pin "65") (pinfunction "65_65") (pintype "power_in"))
      (node (ref "R37") (pin "1") (pinfunction "1_1") (pintype "passive"))
      (node (ref "R79") (pin "1") (pinfunction "1_1") (pintype "passive"))
      (node (ref "U$5") (pin "16") (pinfunction "VDD_16") (pintype "input"))
    )
    (net (code "3") (name "3.3V") (class "Default")
      (node (ref "C38") (pin "2") (pinfunction "2_2") (pintype "passive"))
      (node (ref "C39") (pin "2") (pinfunction "2_2") (pintype "passive"))
      (node (ref "C45") (pin "1") (pinfunction "1_1") (pintype "passive"))
      (node (ref "C46") (pin "1") (pinfunction "1_1") (pintype "passive"))
      (node (ref "C51") (pin "2") (pinfunction "2_2") (pintype "passive"))
      (node (ref "IC1") (pin "2") (pinfunction "OUT_2") (pintype "passive"))
      (node (ref "JP23") (pin "1") (pinfunction "1_1") (pintype "passive"))
      (node (ref "K2") (pin "1") (pinfunction "+_1") (pintype "passive"))
      (node (ref "OK4") (pin "4") (pinfunction "COL_4") (pintype "passive"))
      (node (ref "R62") (pin "1") (pinfunction "1_1") (pintype "passive"))
      (node (ref "R67") (pin "1") (pinfunction "1_1") (pintype "passive"))
      (node (ref "R82") (pin "1") (pinfunction "1_1") (pintype "passive"))
      (node (ref "U$10") (pin "1") (pinfunction "VCC_1") (pintype "bidirectional"))
      (node (ref "U$7") (pin "25") (pinfunction "DVDD_25") (pintype "bidirectional"))
      (node (ref "U$7") (pin "26") (pinfunction "~{MRCL}_26") (pintype "power_in"))
      (node (ref "U$9") (pin "1") (pinfunction "VDD1_1") (pintype "power_in"))
    )
    (net (code "4") (name "AGND") (class "Default")
      (node (ref "C22") (pin "2") (pinfunction "2_2") (pintype "passive"))
      (node (ref "C28") (pin "2") (pinfunction "2_2") (pintype "passive"))
      (node (ref "C31") (pin "2") (pinfunction "2_2") (pintype "passive"))
      (node (ref "C32") (pin "2") (pinfunction "2_2") (pintype "passive"))
      (node (ref "C33") (pin "2") (pinfunction "2_2") (pintype "passive"))
      (node (ref "C36") (pin "1") (pinfunction "1_1") (pintype "passive"))
      (node (ref "C37") (pin "1") (pinfunction "1_1") (pintype "passive"))
      (node (ref "C47") (pin "2") (pinfunction "2_2") (pintype "passive"))
      (node (ref "C48") (pin "2") (pinfunction "2_2") (pintype "passive"))
      (node (ref "L5") (pin "1") (pinfunction "1_1") (pintype "passive"))
      (node (ref "R55") (pin "2") (pinfunction "2_2") (pintype "passive"))
      (node (ref "R56") (pin "2") (pinfunction "2_2") (pintype "passive"))
      (node (ref "U$7") (pin "21") (pinfunction "AGND_21") (pintype "bidirectional"))
    )
    (net (code "5") (name "AN_IN__DIO2") (class "Default")
      (node (ref "R68") (pin "2") (pinfunction "2_2") (pintype "passive"))
      (node (ref "U$7") (pin "20") (pinfunction "AN_IN/DIO2_20") (pintype "power_in"))
    )
    (net (code "6") (name "DATA+") (class "Default")
      (node (ref "IC2") (pin "4") (pinfunction "D+_4") (pintype "bidirectional"))
      (node (ref "J401") (pin "D+") (pinfunction "D+_D+") (pintype "input"))
      (node (ref "U404") (pin "5") (pinfunction "IO2_5") (pintype "bidirectional"))
    )
    (net (code "7") (name "DATA-") (class "Default")
      (node (ref "IC2") (pin "5") (pinfunction "D-_5") (pintype "bidirectional"))
      (node (ref "J401") (pin "D-") (pinfunction "D-_D-") (pintype "input"))
      (node (ref "U404") (pin "3") (pinfunction "IO1_3") (pintype "bidirectional"))
    )
    (net (code "8") (name "DIO0") (class "Default")
      (node (ref "R69") (pin "1") (pinfunction "1_1") (pintype "passive"))
      (node (ref "R72") (pin "1") (pinfunction "1_1") (pintype "passive"))
      (node (ref "U$7") (pin "14") (pinfunction "A0/DIO0_14") (pintype "power_in"))
    )
    (net (code "9") (name "DIO1") (class "Default")
      (node (ref "R70") (pin "1") (pinfunction "1_1") (pintype "passive"))
      (node (ref "R73") (pin "1") (pinfunction "1_1") (pintype "passive"))
      (node (ref "U$7") (pin "15") (pinfunction "A1/DIO1_15") (pintype "power_in"))
    )
    (net (code "10") (name "DIO3") (class "Default")
      (node (ref "R71") (pin "1") (pinfunction "1_1") (pintype "passive"))
      (node (ref "R74") (pin "1") (pinfunction "1_1") (pintype "passive"))
      (node (ref "U$7") (pin "22") (pinfunction "DIO3_22") (pintype "power_in"))
    )
    (net (code "11") (name "GND") (class "Default")
      (node (ref "BQ27510") (pin "1") (pinfunction "BI/TOUT_1") (pintype "bidirectional"))
      (node (ref "BQ27510") (pin "6") (pinfunction "VSS_6") (pintype "power_in"))
      (node (ref "BQ27510") (pin "9") (pinfunction "TS_9") (pintype "output"))
      (node (ref "C1") (pin "2") (pinfunction "2_2") (pintype "passive"))
      (node (ref "C10") (pin "2") (pinfunction "2_2") (pintype "passive"))
      (node (ref "C11") (pin "2") (pinfunction "2_2") (pintype "passive"))
      (node (ref "C12") (pin "2") (pinfunction "2_2") (pintype "passive"))
      (node (ref "C13") (pin "2") (pinfunction "2_2") (pintype "passive"))
      (node (ref "C14") (pin "2") (pinfunction "2_2") (pintype "passive"))
      (node (ref "C15") (pin "2") (pinfunction "2_2") (pintype "passive"))
      (node (ref "C16") (pin "2") (pinfunction "2_2") (pintype "passive"))
      (node (ref "C17") (pin "2") (pinfunction "2_2") (pintype "passive"))
      (node (ref "C18") (pin "1") (pinfunction "1_1") (pintype "passive"))
      (node (ref "C19") (pin "1") (pinfunction "1_1") (pintype "passive"))
      (node (ref "C2") (pin "2") (pinfunction "2_2") (pintype "passive"))
      (node (ref "C20") (pin "2") (pinfunction "2_2") (pintype "passive"))
      (node (ref "C21") (pin "2") (pinfunction "2_2") (pintype "passive"))
      (node (ref "C23") (pin "2") (pinfunction "2_2") (pintype "passive"))
      (node (ref "C24") (pin "2") (pinfunction "2_2") (pintype "passive"))
      (node (ref "C25") (pin "1") (pinfunction "1_1") (pintype "passive"))
      (node (ref "C26") (pin "1") (pinfunction "1_1") (pintype "passive"))
      (node (ref "C27") (pin "-") (pinfunction "-_-") (pintype "passive"))
      (node (ref "C29") (pin "2") (pinfunction "2_2") (pintype "passive"))
      (node (ref "C3") (pin "2") (pinfunction "2_2") (pintype "passive"))
      (node (ref "C30") (pin "-") (pinfunction "-_-") (pintype "passive"))
      (node (ref "C40") (pin "1") (pinfunction "1_1") (pintype "passive"))
      (node (ref "C403") (pin "-") (pinfunction "-_-") (pintype "passive"))
      (node (ref "C49") (pin "-") (pinfunction "-_-") (pintype "passive"))
      (node (ref "C5") (pin "2") (pinfunction "2_2") (pintype "passive"))
      (node (ref "C50") (pin "2") (pinfunction "2_2") (pintype "passive"))
      (node (ref "C6") (pin "1") (pinfunction "1_1") (pintype "passive"))
      (node (ref "C7") (pin "2") (pinfunction "2_2") (pintype "passive"))
      (node (ref "C8") (pin "2") (pinfunction "2_2") (pintype "passive"))
      (node (ref "C9") (pin "2") (pinfunction "2_2") (pintype "passive"))
      (node (ref "CN1") (pin "GND") (pinfunction "GNDBREAK_GND") (pintype "power_in"))
      (node (ref "CN1") (pin "GNDBREAK") (pinfunction "GND_GNDBREAK") (pintype "power_in"))
      (node (ref "IC2") (pin "3") (pinfunction "GND_3") (pintype "power_in"))
      (node (ref "IC2") (pin "EXP") (pinfunction "GND_EXP") (pintype "power_in"))
      (node (ref "IC2") (pin "EXP@0") (pinfunction "GND_EXP@0") (pintype "power_in"))
      (node (ref "IC2") (pin "M") (pinfunction "GND_M") (pintype "power_in"))
      (node (ref "J401") (pin "GND") (pinfunction "GND_GND") (pintype "input"))
      (node (ref "JP1") (pin "1") (pinfunction "1_1") (pintype "passive"))
      (node (ref "JP10") (pin "1") (pinfunction "1_1") (pintype "passive"))
      (node (ref "JP11") (pin "3") (pinfunction "3_3") (pintype "passive"))
      (node (ref "JP12") (pin "1") (pinfunction "1_1") (pintype "passive"))
      (node (ref "JP13") (pin "3") (pinfunction "3_3") (pintype "passive"))
      (node (ref "JP18") (pin "1") (pinfunction "1_1") (pintype "passive"))
      (node (ref "JP19") (pin "1") (pinfunction "1_1") (pintype "passive"))
      (node (ref "JP2") (pin "3") (pinfunction "3_3") (pintype "passive"))
      (node (ref "JP21") (pin "1") (pinfunction "1_1") (pintype "passive"))
      (node (ref "JP22") (pin "1") (pinfunction "1_1") (pintype "passive"))
      (node (ref "JP24") (pin "2") (pinfunction "2_2") (pintype "passive"))
      (node (ref "JP3") (pin "3") (pinfunction "3_3") (pintype "passive"))
      (node (ref "JP4") (pin "1") (pinfunction "1_1") (pintype "passive"))
      (node (ref "JP5") (pin "4") (pinfunction "4_4") (pintype "passive"))
      (node (ref "JP6") (pin "3") (pinfunction "3_3") (pintype "passive"))
      (node (ref "JP7") (pin "3") (pinfunction "3_3") (pintype "passive"))
      (node (ref "JP8") (pin "1") (pinfunction "1_1") (pintype "passive"))
      (node (ref "JP9") (pin "1") (pinfunction "1_1") (pintype "passive"))
      (node (ref "MSP430F5529") (pin "14") (pinfunction "14_14") (pintype "power_in"))
      (node (ref "MSP430F5529") (pin "19") (pinfunction "19_19") (pintype "power_in"))
      (node (ref "MSP430F5529") (pin "49") (pinfunction "49_49") (pintype "power_in"))
      (node (ref "MSP430F5529") (pin "61") (pinfunction "61_61") (pintype "power_in"))
      (node (ref "MSP430F5529") (pin "68") (pinfunction "68_68") (pintype "power_in"))
      (node (ref "NRF24L01") (pin "1") (pinfunction "GND_1") (pintype "power_in"))
      (node (ref "OK4") (pin "2") (pinfunction "C_2") (pintype "passive"))
      (node (ref "Q1") (pin "3") (pinfunction "S_3") (pintype "passive"))
      (node (ref "Q2") (pin "P3") (pinfunction "GND_P3") (pintype "power_in"))
      (node (ref "Q4") (pin "2") (pinfunction "2_2") (pintype "passive"))
      (node (ref "Q5") (pin "3") (pinfunction "S_3") (pintype "passive"))
      (node (ref "R1") (pin "1") (pinfunction "1_1") (pintype "passive"))
      (node (ref "R10") (pin "1") (pinfunction "1_1") (pintype "passive"))
      (node (ref "R11") (pin "1") (pinfunction "1_1") (pintype "passive"))
      (node (ref "R16") (pin "1") (pinfunction "1_1") (pintype "passive"))
      (node (ref "R17") (pin "2") (pinfunction "2_2") (pintype "passive"))
      (node (ref "R20") (pin "2") (pinfunction "2_2") (pintype "passive"))
      (node (ref "R29") (pin "2") (pinfunction "2_2") (pintype "passive"))
      (node (ref "R3") (pin "1") (pinfunction "1_1") (pintype "passive"))
      (node (ref "R39") (pin "1") (pinfunction "1_1") (pintype "passive"))
      (node (ref "R401") (pin "2") (pinfunction "2_2") (pintype "passive"))
      (node (ref "R78") (pin "1") (pinfunction "1_1") (pintype "passive"))
      (node (ref "R81") (pin "2") (pinfunction "2_2") (pintype "passive"))
      (node (ref "R85") (pin "1") (pinfunction "1_1") (pintype "passive"))
      (node (ref "R87") (pin "1") (pinfunction "1_1") (pintype "passive"))
      (node (ref "S3") (pin "1") (pinfunction "P_1") (pintype "passive"))
      (node (ref "T1") (pin "2") (pinfunction "E_2") (pintype "passive"))
      (node (ref "T2") (pin "2") (pinfunction "E_2") (pintype "passive"))
      (node (ref "T3") (pin "2") (pinfunction "E_2") (pintype "passive"))
      (node (ref "T4") (pin "2") (pinfunction "E_2") (pintype "passive"))
      (node (ref "T5") (pin "2") (pinfunction "E_2") (pintype "passive"))
      (node (ref "T6") (pin "2") (pinfunction "E_2") (pintype "passive"))
      (node (ref "TPS63001") (pin "3") (pinfunction "PGND_3") (pintype "power_in"))
      (node (ref "TPS63001") (pin "9") (pinfunction "GND_9") (pintype "power_in"))
      (node (ref "TPS63002") (pin "3") (pinfunction "PGND_3") (pintype "power_in"))
      (node (ref "TPS63002") (pin "9") (pinfunction "GND_9") (pintype "power_in"))
      (node (ref "TPS63061") (pin "3") (pinfunction "PGND_3") (pintype "power_in"))
      (node (ref "TPS63061") (pin "6") (pinfunction "EN_6") (pintype "input"))
      (node (ref "TPS63061") (pin "9") (pinfunction "GND_9") (pintype "power_in"))
      (node (ref "U$5") (pin "8") (pinfunction "VSS_8") (pintype "tri_state"))
      (node (ref "U$9") (pin "5") (pinfunction "GND2_5") (pintype "power_in"))
      (node (ref "U1") (pin "3") (pinfunction "VSS_3") (pintype "passive"))
      (node (ref "U404") (pin "4") (pinfunction "GND_4") (pintype "power_in"))
      (node (ref "U5") (pin "1") (pinfunction "E0_1") (pintype "input"))
      (node (ref "U5") (pin "2") (pinfunction "E1_2") (pintype "input"))
      (node (ref "U5") (pin "3") (pinfunction "E2_3") (pintype "power_in"))
      (node (ref "U5") (pin "4") (pinfunction "VSS_4") (pintype "input"))
      (node (ref "U5") (pin "7") (pinfunction "WC_7") (pintype "output"))
    )
    (net (code "12") (name "GNDA") (class "Default")
      (node (ref "C34") (pin "2") (pinfunction "2_2") (pintype "passive"))
      (node (ref "C35") (pin "2") (pinfunction "2_2") (pintype "passive"))
      (node (ref "C38") (pin "1") (pinfunction "1_1") (pintype "passive"))
      (node (ref "C39") (pin "1") (pinfunction "1_1") (pintype "passive"))
      (node (ref "C43") (pin "-") (pinfunction "-_-") (pintype "passive"))
      (node (ref "C44") (pin "2") (pinfunction "2_2") (pintype "passive"))
      (node (ref "C45") (pin "2") (pinfunction "2_2") (pintype "passive"))
      (node (ref "C46") (pin "2") (pinfunction "2_2") (pintype "passive"))
      (node (ref "C51") (pin "1") (pinfunction "1_1") (pintype "passive"))
      (node (ref "D4") (pin "A") (pinfunction "A_A") (pintype "passive"))
      (node (ref "IC1") (pin "1") (pinfunction "GND_1") (pintype "input"))
      (node (ref "IC3") (pin "2") (pinfunction "GND_2") (pintype "passive"))
      (node (ref "JP20") (pin "1") (pinfunction "1_1") (pintype "passive"))
      (node (ref "JP23") (pin "2") (pinfunction "2_2") (pintype "passive"))
      (node (ref "L4") (pin "2") (pinfunction "2_2") (pintype "passive"))
      (node (ref "L5") (pin "2") (pinfunction "2_2") (pintype "passive"))
      (node (ref "LED6") (pin "C") (pinfunction "C_C") (pintype "passive"))
      (node (ref "LED7") (pin "C") (pinfunction "C_C") (pintype "passive"))
      (node (ref "LED8") (pin "C") (pinfunction "C_C") (pintype "passive"))
      (node (ref "LED9") (pin "C") (pinfunction "C_C") (pintype "passive"))
      (node (ref "OK1") (pin "2") (pinfunction "C_2") (pintype "passive"))
      (node (ref "OK2") (pin "2") (pinfunction "C_2") (pintype "passive"))
      (node (ref "OK3") (pin "2") (pinfunction "C_2") (pintype "passive"))
      (node (ref "R61") (pin "2") (pinfunction "2_2") (pintype "passive"))
      (node (ref "R78") (pin "2") (pinfunction "2_2") (pintype "passive"))
      (node (ref "R81") (pin "1") (pinfunction "1_1") (pintype "passive"))
      (node (ref "U$10") (pin "3") (pinfunction "GND_3") (pintype "bidirectional"))
      (node (ref "U$7") (pin "24") (pinfunction "DGND_24") (pintype "bidirectional"))
      (node (ref "U$7") (pin "27") (pinfunction "DGND_27") (pintype "bidirectional"))
      (node (ref "U$7") (pin "M@0") (pinfunction "EP_M@0") (pintype "bidirectional"))
      (node (ref "U$7") (pin "M@1") (pinfunction "EP_M@1") (pintype "bidirectional"))
      (node (ref "U$7") (pin "M@2") (pinfunction "EP_M@2") (pintype "bidirectional"))
      (node (ref "U$7") (pin "M@3") (pinfunction "EP_M@3") (pintype "bidirectional"))
      (node (ref "U$7") (pin "M@4") (pinfunction "EP_M@4") (pintype "bidirectional"))
      (node (ref "U$7") (pin "M@5") (pinfunction "EP_M@5") (pintype "bidirectional"))
      (node (ref "U$9") (pin "4") (pinfunction "GND1_4") (pintype "power_in"))
    )
    (net (code "13") (name "HUB_DM1") (class "Default")
      (node (ref "R31") (pin "1") (pinfunction "1_1") (pintype "passive"))
    )
    (net (code "14") (name "HUB_DP1") (class "Default")
      (node (ref "R32") (pin "1") (pinfunction "1_1") (pintype "passive"))
    )
    (net (code "15") (name "LINE") (class "Default")
      (node (ref "C41") (pin "1") (pinfunction "1_1") (pintype "passive"))
      (node (ref "K2") (pin "3") (pinfunction "P_3") (pintype "passive"))
      (node (ref "L3") (pin "1") (pinfunction "1_1") (pintype "passive"))
      (node (ref "R64") (pin "2") (pinfunction "2_2") (pintype "passive"))
      (node (ref "X2") (pin "1") (pinfunction "1_1") (pintype "passive"))
    )
    (net (code "16") (name "NEUTRAL") (class "Default")
      (node (ref "C41") (pin "2") (pinfunction "2_2") (pintype "passive"))
      (node (ref "L1") (pin "1") (pinfunction "1_1") (pintype "passive"))
      (node (ref "L4") (pin "1") (pinfunction "1_1") (pintype "passive"))
      (node (ref "R57") (pin "2") (pinfunction "2_2") (pintype "passive"))
      (node (ref "R64") (pin "1") (pinfunction "1_1") (pintype "passive"))
      (node (ref "TP4") (pin "TP") (pinfunction "TP_TP") (pintype "input"))
      (node (ref "X2") (pin "3") (pinfunction "1_3") (pintype "passive"))
    )
    (net (code "17") (name "N_OUT") (class "Default")
      (node (ref "K2") (pin "6") (pinfunction "P_6") (pintype "passive"))
      (node (ref "L2") (pin "1") (pinfunction "1_1") (pintype "passive"))
      (node (ref "R57") (pin "1") (pinfunction "1_1") (pintype "passive"))
      (node (ref "TP5") (pin "TP") (pinfunction "TP_TP") (pintype "input"))
    )
    (net (code "18") (name "Net-(BQ27510A-REG25)") (class "Default")
      (node (ref "BQ27510") (pin "2") (pinfunction "REG25_2") (pintype "input"))
      (node (ref "BQ27510") (pin "5") (pinfunction "VCC_5") (pintype "power_in"))
      (node (ref "C2") (pin "1") (pinfunction "1_1") (pintype "passive"))
    )
    (net (code "19") (name "Net-(BQ27510A-SRN)") (class "Default")
      (node (ref "BQ27510") (pin "8") (pinfunction "SRN_8") (pintype "input"))
      (node (ref "C4") (pin "1") (pinfunction "1_1") (pintype "passive"))
      (node (ref "C5") (pin "1") (pinfunction "1_1") (pintype "passive"))
      (node (ref "R10") (pin "2") (pinfunction "2_2") (pintype "passive"))
    )
    (net (code "20") (name "Net-(BQ27510A-SRP)") (class "Default")
      (node (ref "BQ27510") (pin "7") (pinfunction "SRP_7") (pintype "output"))
      (node (ref "C4") (pin "2") (pinfunction "2_2") (pintype "passive"))
      (node (ref "C6") (pin "2") (pinfunction "2_2") (pintype "passive"))
      (node (ref "R12") (pin "1") (pinfunction "1_1") (pintype "passive"))
    )
    (net (code "21") (name "Net-(C15-Pad1)") (class "Default")
      (node (ref "C15") (pin "1") (pinfunction "1_1") (pintype "passive"))
      (node (ref "MSP430F5529") (pin "67") (pinfunction "67_67") (pintype "power_in"))
    )
    (net (code "22") (name "Net-(C16-Pad1)") (class "Default")
      (node (ref "C16") (pin "1") (pinfunction "1_1") (pintype "passive"))
      (node (ref "MSP430F5529") (pin "66") (pinfunction "66_66") (pintype "power_in"))
    )
    (net (code "23") (name "Net-(C18-Pad2)") (class "Default")
      (node (ref "C18") (pin "2") (pinfunction "2_2") (pintype "passive"))
      (node (ref "MSP430F5529") (pin "20") (pinfunction "20_20") (pintype "power_in"))
    )
    (net (code "24") (name "Net-(C29-Pad1)") (class "Default")
      (node (ref "C29") (pin "1") (pinfunction "1_1") (pintype "passive"))
      (node (ref "MSP430F5529") (pin "11") (pinfunction "11_11") (pintype "power_in"))
      (node (ref "R28") (pin "1") (pinfunction "1_1") (pintype "passive"))
    )
    (net (code "25") (name "Net-(C42-Pad1)") (class "Default")
      (node (ref "C42") (pin "1") (pinfunction "1_1") (pintype "passive"))
      (node (ref "R65") (pin "2") (pinfunction "2_2") (pintype "passive"))
    )
    (net (code "26") (name "Net-(C42-Pad2)") (class "Default")
      (node (ref "C42") (pin "2") (pinfunction "2_2") (pintype "passive"))
      (node (ref "D4") (pin "C") (pinfunction "C_C") (pintype "passive"))
      (node (ref "D5") (pin "A") (pinfunction "A_A") (pintype "passive"))
    )
    (net (code "27") (name "Net-(D1-C)") (class "Default")
      (node (ref "D1") (pin "A") (pinfunction "C_A") (pintype "passive"))
      (node (ref "R30") (pin "2") (pinfunction "2_2") (pintype "passive"))
    )
    (net (code "28") (name "Net-(D2-C)") (class "Default")
      (node (ref "D2") (pin "A") (pinfunction "C_A") (pintype "passive"))
      (node (ref "R18") (pin "2") (pinfunction "2_2") (pintype "passive"))
    )
    (net (code "29") (name "Net-(D3-C)") (class "Default")
      (node (ref "D3") (pin "A") (pinfunction "C_A") (pintype "passive"))
      (node (ref "R21") (pin "2") (pinfunction "2_2") (pintype "passive"))
    )
    (net (code "30") (name "Net-(D6-PadA)") (class "Default")
      (node (ref "D6") (pin "A") (pinfunction "A_A") (pintype "passive"))
      (node (ref "JP20") (pin "2") (pinfunction "2_2") (pintype "passive"))
      (node (ref "R79") (pin "2") (pinfunction "2_2") (pintype "passive"))
    )
    (net (code "31") (name "Net-(D6-PadC)") (class "Default")
      (node (ref "D6") (pin "C") (pinfunction "C_C") (pintype "passive"))
      (node (ref "R66") (pin "2") (pinfunction "2_2") (pintype "passive"))
    )
    (net (code "32") (name "Net-(D8-A)") (class "Default")
      (node (ref "D8") (pin "1") (pinfunction "A_1") (pintype "passive"))
      (node (ref "J401") (pin "VBUS") (pinfunction "VBUS_VBUS") (pintype "input"))
      (node (ref "R86") (pin "1") (pinfunction "1_1") (pintype "passive"))
    )
    (net (code "33") (name "Net-(IC1-IN)") (class "Default")
      (node (ref "C43") (pin "+") (pinfunction "+_+") (pintype "passive"))
      (node (ref "C44") (pin "1") (pinfunction "1_1") (pintype "passive"))
      (node (ref "D5") (pin "C") (pinfunction "C_C") (pintype "passive"))
      (node (ref "IC1") (pin "3") (pinfunction "IN_3") (pintype "input"))
      (node (ref "R66") (pin "1") (pinfunction "1_1") (pintype "passive"))
    )
    (net (code "34") (name "Net-(IC2-VDD)") (class "Default")
      (node (ref "C11") (pin "1") (pinfunction "1_1") (pintype "passive"))
      (node (ref "IC2") (pin "6") (pinfunction "VDD_6") (pintype "power_in"))
    )
    (net (code "35") (name "Net-(IC3-VOUT)") (class "Default")
      (node (ref "IC3") (pin "3") (pinfunction "VOUT_3") (pintype "passive"))
      (node (ref "K2") (pin "8") (pinfunction "-_8") (pintype "passive"))
    )
    (net (code "36") (name "Net-(J401-PadSHIELD1)") (class "Default")
      (node (ref "J401") (pin "SHIELD1") (pinfunction "SHIELD1_SHIELD1") (pintype "bidirectional"))
      (node (ref "R401") (pin "1") (pinfunction "1_1") (pintype "passive"))
    )
    (net (code "37") (name "Net-(JP14-Pad1)") (class "Default")
      (node (ref "JP14") (pin "1") (pinfunction "1_1") (pintype "passive"))
      (node (ref "R44") (pin "1") (pinfunction "1_1") (pintype "passive"))
    )
    (net (code "38") (name "Net-(JP14-Pad2)") (class "Default")
      (node (ref "JP14") (pin "2") (pinfunction "2_2") (pintype "passive"))
      (node (ref "R45") (pin "1") (pinfunction "1_1") (pintype "passive"))
    )
    (net (code "39") (name "Net-(JP14-Pad3)") (class "Default")
      (node (ref "JP14") (pin "3") (pinfunction "3_3") (pintype "passive"))
      (node (ref "R46") (pin "1") (pinfunction "1_1") (pintype "passive"))
    )
    (net (code "40") (name "Net-(K2A-S)") (class "Default")
      (node (ref "K2") (pin "4") (pinfunction "S_4") (pintype "passive"))
      (node (ref "X3") (pin "3") (pinfunction "1_3") (pintype "passive"))
    )
    (net (code "41") (name "Net-(K2B-S)") (class "Default")
      (node (ref "K2") (pin "5") (pinfunction "S_5") (pintype "passive"))
      (node (ref "X3") (pin "1") (pinfunction "1_1") (pintype "passive"))
    )
    (net (code "42") (name "Net-(L1-Pad2)") (class "Default")
      (node (ref "L1") (pin "2") (pinfunction "2_2") (pintype "passive"))
      (node (ref "R58") (pin "1") (pinfunction "1_1") (pintype "passive"))
      (node (ref "R59") (pin "1") (pinfunction "1_1") (pintype "passive"))
    )
    (net (code "43") (name "Net-(L2-Pad2)") (class "Default")
      (node (ref "L2") (pin "2") (pinfunction "2_2") (pintype "passive"))
      (node (ref "R58") (pin "2") (pinfunction "2_2") (pintype "passive"))
      (node (ref "R60") (pin "1") (pinfunction "1_1") (pintype "passive"))
    )
    (net (code "44") (name "Net-(LED1-PadA)") (class "Default")
      (node (ref "LED1") (pin "A") (pinfunction "A_A") (pintype "passive"))
      (node (ref "R4") (pin "1") (pinfunction "1_1") (pintype "passive"))
    )
    (net (code "45") (name "Net-(LED2-PadA)") (class "Default")
      (node (ref "LED2") (pin "A") (pinfunction "A_A") (pintype "passive"))
      (node (ref "R7") (pin "1") (pinfunction "1_1") (pintype "passive"))
    )
    (net (code "46") (name "Net-(LED3-PadC)") (class "Default")
      (node (ref "LED3") (pin "C") (pinfunction "C_C") (pintype "passive"))
      (node (ref "R50") (pin "1") (pinfunction "1_1") (pintype "passive"))
    )
    (net (code "47") (name "Net-(LED4-PadC)") (class "Default")
      (node (ref "LED4") (pin "C") (pinfunction "C_C") (pintype "passive"))
      (node (ref "R49") (pin "1") (pinfunction "1_1") (pintype "passive"))
    )
    (net (code "48") (name "Net-(LED5-PadC)") (class "Default")
      (node (ref "LED5") (pin "C") (pinfunction "C_C") (pintype "passive"))
      (node (ref "R51") (pin "1") (pinfunction "1_1") (pintype "passive"))
    )
    (net (code "49") (name "Net-(LED6-PadA)") (class "Default")
      (node (ref "LED6") (pin "A") (pinfunction "A_A") (pintype "passive"))
      (node (ref "R63") (pin "1") (pinfunction "1_1") (pintype "passive"))
    )
    (net (code "50") (name "Net-(LED7-PadA)") (class "Default")
      (node (ref "LED7") (pin "A") (pinfunction "A_A") (pintype "passive"))
      (node (ref "R69") (pin "2") (pinfunction "2_2") (pintype "passive"))
    )
    (net (code "51") (name "Net-(LED8-PadA)") (class "Default")
      (node (ref "LED8") (pin "A") (pinfunction "A_A") (pintype "passive"))
      (node (ref "R70") (pin "2") (pinfunction "2_2") (pintype "passive"))
    )
    (net (code "52") (name "Net-(LED9-PadA)") (class "Default")
      (node (ref "LED9") (pin "A") (pinfunction "A_A") (pintype "passive"))
      (node (ref "R71") (pin "2") (pinfunction "2_2") (pintype "passive"))
    )
    (net (code "53") (name "Net-(MSP430F5529-Pad69)") (class "Default")
      (node (ref "MSP430F5529") (pin "69") (pinfunction "69_69") (pintype "bidirectional"))
      (node (ref "Q4") (pin "3") (pinfunction "3_3") (pintype "passive"))
    )
    (net (code "54") (name "Net-(MSP430F5529-Pad70)") (class "Default")
      (node (ref "MSP430F5529") (pin "70") (pinfunction "70_70") (pintype "bidirectional"))
      (node (ref "Q4") (pin "1") (pinfunction "1_1") (pintype "passive"))
    )
    (net (code "55") (name "Net-(OK1-A)") (class "Default")
      (node (ref "OK1") (pin "1") (pinfunction "A_1") (pintype "passive"))
      (node (ref "R73") (pin "2") (pinfunction "2_2") (pintype "passive"))
    )
    (net (code "56") (name "Net-(OK1-COL)") (class "Default")
      (node (ref "JP16") (pin "1") (pinfunction "1_1") (pintype "passive"))
      (node (ref "OK1") (pin "4") (pinfunction "COL_4") (pintype "passive"))
    )
    (net (code "57") (name "Net-(OK1-EMIT)") (class "Default")
      (node (ref "JP16") (pin "2") (pinfunction "2_2") (pintype "passive"))
      (node (ref "OK1") (pin "3") (pinfunction "EMIT_3") (pintype "passive"))
    )
    (net (code "58") (name "Net-(OK2-A)") (class "Default")
      (node (ref "OK2") (pin "1") (pinfunction "A_1") (pintype "passive"))
      (node (ref "R72") (pin "2") (pinfunction "2_2") (pintype "passive"))
    )
    (net (code "59") (name "Net-(OK2-COL)") (class "Default")
      (node (ref "JP15") (pin "1") (pinfunction "1_1") (pintype "passive"))
      (node (ref "OK2") (pin "4") (pinfunction "COL_4") (pintype "passive"))
    )
    (net (code "60") (name "Net-(OK2-EMIT)") (class "Default")
      (node (ref "JP15") (pin "2") (pinfunction "2_2") (pintype "passive"))
      (node (ref "OK2") (pin "3") (pinfunction "EMIT_3") (pintype "passive"))
    )
    (net (code "61") (name "Net-(OK3-A)") (class "Default")
      (node (ref "OK3") (pin "1") (pinfunction "A_1") (pintype "passive"))
      (node (ref "R74") (pin "2") (pinfunction "2_2") (pintype "passive"))
    )
    (net (code "62") (name "Net-(OK3-COL)") (class "Default")
      (node (ref "JP17") (pin "1") (pinfunction "1_1") (pintype "passive"))
      (node (ref "OK3") (pin "4") (pinfunction "COL_4") (pintype "passive"))
    )
    (net (code "63") (name "Net-(OK3-EMIT)") (class "Default")
      (node (ref "JP17") (pin "2") (pinfunction "2_2") (pintype "passive"))
      (node (ref "OK3") (pin "3") (pinfunction "EMIT_3") (pintype "passive"))
    )
    (net (code "64") (name "Net-(Q1-G)") (class "Default")
      (node (ref "Q1") (pin "1") (pinfunction "G_1") (pintype "passive"))
      (node (ref "R85") (pin "2") (pinfunction "2_2") (pintype "passive"))
      (node (ref "R88") (pin "1") (pinfunction "1_1") (pintype "passive"))
    )
    (net (code "65") (name "Net-(Q2-1)") (class "Default")
      (node (ref "C25") (pin "2") (pinfunction "2_2") (pintype "passive"))
      (node (ref "MSP430F5529") (pin "13") (pinfunction "13_13") (pintype "bidirectional"))
      (node (ref "Q2") (pin "P1") (pinfunction "1_P1") (pintype "bidirectional"))
    )
    (net (code "66") (name "Net-(Q2-2)") (class "Default")
      (node (ref "C26") (pin "2") (pinfunction "2_2") (pintype "passive"))
      (node (ref "MSP430F5529") (pin "12") (pinfunction "12_12") (pintype "bidirectional"))
      (node (ref "Q2") (pin "P2") (pinfunction "2_P2") (pintype "bidirectional"))
    )
    (net (code "67") (name "Net-(Q5-G)") (class "Default")
      (node (ref "Q5") (pin "1") (pinfunction "G_1") (pintype "passive"))
      (node (ref "R87") (pin "2") (pinfunction "2_2") (pintype "passive"))
      (node (ref "R90") (pin "1") (pinfunction "1_1") (pintype "passive"))
    )
    (net (code "68") (name "Net-(R53-Pad2)") (class "Default")
      (node (ref "R53") (pin "2") (pinfunction "2_2") (pintype "passive"))
      (node (ref "R54") (pin "1") (pinfunction "1_1") (pintype "passive"))
    )
    (net (code "69") (name "Net-(S5-S)") (class "Default")
      (node (ref "R14") (pin "1") (pinfunction "1_1") (pintype "passive"))
      (node (ref "S5") (pin "2") (pinfunction "S_2") (pintype "passive"))
    )
    (net (code "70") (name "Net-(T1-B)") (class "Default")
      (node (ref "R41") (pin "2") (pinfunction "2_2") (pintype "passive"))
      (node (ref "T1") (pin "1") (pinfunction "B_1") (pintype "passive"))
    )
    (net (code "71") (name "Net-(T1-C)") (class "Default")
      (node (ref "R44") (pin "2") (pinfunction "2_2") (pintype "passive"))
      (node (ref "T1") (pin "3") (pinfunction "C_3") (pintype "passive"))
    )
    (net (code "72") (name "Net-(T2-B)") (class "Default")
      (node (ref "R42") (pin "2") (pinfunction "2_2") (pintype "passive"))
      (node (ref "T2") (pin "1") (pinfunction "B_1") (pintype "passive"))
    )
    (net (code "73") (name "Net-(T2-C)") (class "Default")
      (node (ref "R45") (pin "2") (pinfunction "2_2") (pintype "passive"))
      (node (ref "T2") (pin "3") (pinfunction "C_3") (pintype "passive"))
    )
    (net (code "74") (name "Net-(T3-B)") (class "Default")
      (node (ref "R43") (pin "2") (pinfunction "2_2") (pintype "passive"))
      (node (ref "T3") (pin "1") (pinfunction "B_1") (pintype "passive"))
    )
    (net (code "75") (name "Net-(T3-C)") (class "Default")
      (node (ref "R46") (pin "2") (pinfunction "2_2") (pintype "passive"))
      (node (ref "T3") (pin "3") (pinfunction "C_3") (pintype "passive"))
    )
    (net (code "76") (name "Net-(T4-B)") (class "Default")
      (node (ref "R52") (pin "2") (pinfunction "2_2") (pintype "passive"))
      (node (ref "T4") (pin "1") (pinfunction "B_1") (pintype "passive"))
    )
    (net (code "77") (name "Net-(T4-C)") (class "Default")
      (node (ref "R49") (pin "2") (pinfunction "2_2") (pintype "passive"))
      (node (ref "T4") (pin "3") (pinfunction "C_3") (pintype "passive"))
    )
    (net (code "78") (name "Net-(T5-B)") (class "Default")
      (node (ref "R47") (pin "2") (pinfunction "2_2") (pintype "passive"))
      (node (ref "T5") (pin "1") (pinfunction "B_1") (pintype "passive"))
    )
    (net (code "79") (name "Net-(T5-C)") (class "Default")
      (node (ref "R50") (pin "2") (pinfunction "2_2") (pintype "passive"))
      (node (ref "T5") (pin "3") (pinfunction "C_3") (pintype "passive"))
    )
    (net (code "80") (name "Net-(T6-B)") (class "Default")
      (node (ref "R48") (pin "2") (pinfunction "2_2") (pintype "passive"))
      (node (ref "T6") (pin "1") (pinfunction "B_1") (pintype "passive"))
    )
    (net (code "81") (name "Net-(T6-C)") (class "Default")
      (node (ref "R51") (pin "2") (pinfunction "2_2") (pintype "passive"))
      (node (ref "T6") (pin "3") (pinfunction "C_3") (pintype "passive"))
    )
    (net (code "82") (name "Net-(TPS63001A-FB)") (class "Default")
      (node (ref "C7") (pin "1") (pinfunction "1_1") (pintype "passive"))
      (node (ref "R18") (pin "1") (pinfunction "1_1") (pintype "passive"))
      (node (ref "TPS63001") (pin "1") (pinfunction "VOUT_1") (pintype "output"))
      (node (ref "TPS63001") (pin "10") (pinfunction "FB_10") (pintype "input"))
    )
    (net (code "83") (name "Net-(TPS63001A-L1)") (class "Default")
      (node (ref "TPS63001") (pin "4") (pinfunction "L1_4") (pintype "passive"))
      (node (ref "U$3") (pin "P$1") (pinfunction "1_P$1") (pintype "passive"))
    )
    (net (code "84") (name "Net-(TPS63001A-L2)") (class "Default")
      (node (ref "TPS63001") (pin "2") (pinfunction "L2_2") (pintype "passive"))
      (node (ref "U$3") (pin "P$2") (pinfunction "2_P$2") (pintype "passive"))
    )
    (net (code "85") (name "Net-(TPS63001A-PS{slash}SYNC)") (class "Default")
      (node (ref "R13") (pin "2") (pinfunction "2_2") (pintype "passive"))
      (node (ref "R17") (pin "1") (pinfunction "1_1") (pintype "passive"))
      (node (ref "TPS63001") (pin "7") (pinfunction "PS/SYNC_7") (pintype "input"))
    )
    (net (code "86") (name "Net-(TPS63002A-FB)") (class "Default")
      (node (ref "C9") (pin "1") (pinfunction "1_1") (pintype "passive"))
      (node (ref "R21") (pin "1") (pinfunction "1_1") (pintype "passive"))
      (node (ref "TPS63002") (pin "1") (pinfunction "VOUT_1") (pintype "output"))
      (node (ref "TPS63002") (pin "10") (pinfunction "FB_10") (pintype "input"))
    )
    (net (code "87") (name "Net-(TPS63002A-L1)") (class "Default")
      (node (ref "TPS63002") (pin "4") (pinfunction "L1_4") (pintype "passive"))
      (node (ref "U$4") (pin "P$1") (pinfunction "1_P$1") (pintype "passive"))
    )
    (net (code "88") (name "Net-(TPS63002A-L2)") (class "Default")
      (node (ref "TPS63002") (pin "2") (pinfunction "L2_2") (pintype "passive"))
      (node (ref "U$4") (pin "P$2") (pinfunction "2_P$2") (pintype "passive"))
    )
    (net (code "89") (name "Net-(TPS63002A-PS{slash}SYNC)") (class "Default")
      (node (ref "R19") (pin "2") (pinfunction "2_2") (pintype "passive"))
      (node (ref "R20") (pin "1") (pinfunction "1_1") (pintype "passive"))
      (node (ref "TPS63002") (pin "7") (pinfunction "PS/SYNC_7") (pintype "input"))
    )
    (net (code "90") (name "Net-(TPS63061A-FB)") (class "Default")
      (node (ref "C20") (pin "1") (pinfunction "1_1") (pintype "passive"))
      (node (ref "R30") (pin "1") (pinfunction "1_1") (pintype "passive"))
      (node (ref "TPS63061") (pin "1") (pinfunction "VOUT_1") (pintype "output"))
      (node (ref "TPS63061") (pin "10") (pinfunction "FB_10") (pintype "input"))
    )
    (net (code "91") (name "Net-(TPS63061A-L1)") (class "Default")
      (node (ref "TPS63061") (pin "4") (pinfunction "L1_4") (pintype "passive"))
      (node (ref "U$6") (pin "P$1") (pinfunction "1_P$1") (pintype "passive"))
    )
    (net (code "92") (name "Net-(TPS63061A-L2)") (class "Default")
      (node (ref "TPS63061") (pin "2") (pinfunction "L2_2") (pintype "passive"))
      (node (ref "U$6") (pin "P$2") (pinfunction "2_P$2") (pintype "passive"))
    )
    (net (code "93") (name "Net-(TPS63061A-PS{slash}SYNC)") (class "Default")
      (node (ref "R26") (pin "2") (pinfunction "2_2") (pintype "passive"))
      (node (ref "R29") (pin "1") (pinfunction "1_1") (pintype "passive"))
      (node (ref "TPS63061") (pin "7") (pinfunction "PS/SYNC_7") (pintype "input"))
    )
    (net (code "94") (name "Net-(U$5-SELECT)") (class "Default")
      (node (ref "R37") (pin "2") (pinfunction "2_2") (pintype "passive"))
      (node (ref "R38") (pin "2") (pinfunction "2_2") (pintype "passive"))
      (node (ref "R39") (pin "2") (pinfunction "2_2") (pintype "passive"))
      (node (ref "R40") (pin "2") (pinfunction "2_2") (pintype "passive"))
      (node (ref "U$5") (pin "13") (pinfunction "SELECT_13") (pintype "input"))
    )
    (net (code "95") (name "Net-(U$7-COMMON_A)") (class "Default")
      (node (ref "TP2") (pin "TP") (pinfunction "TP_TP") (pintype "input"))
      (node (ref "U$7") (pin "13") (pinfunction "COMMON_B_13") (pintype "power_in"))
      (node (ref "U$7") (pin "5") (pinfunction "COMMON_A_5") (pintype "power_in"))
    )
    (net (code "96") (name "Net-(U$7-I1+)") (class "Default")
      (node (ref "C32") (pin "1") (pinfunction "1_1") (pintype "passive"))
      (node (ref "R59") (pin "2") (pinfunction "2_2") (pintype "passive"))
      (node (ref "U$7") (pin "16") (pinfunction "I1+_16") (pintype "bidirectional"))
    )
    (net (code "97") (name "Net-(U$7-I1-)") (class "Default")
      (node (ref "C33") (pin "1") (pinfunction "1_1") (pintype "passive"))
      (node (ref "R60") (pin "2") (pinfunction "2_2") (pintype "passive"))
      (node (ref "U$7") (pin "17") (pinfunction "I1-_17") (pintype "bidirectional"))
    )
    (net (code "98") (name "Net-(U$7-MODE{slash}DIR)") (class "Default")
      (node (ref "R61") (pin "1") (pinfunction "1_1") (pintype "passive"))
      (node (ref "R62") (pin "2") (pinfunction "2_2") (pintype "passive"))
      (node (ref "R63") (pin "2") (pinfunction "2_2") (pintype "passive"))
      (node (ref "U$7") (pin "1") (pinfunction "MODE/DIR_1") (pintype "bidirectional"))
    )
    (net (code "99") (name "Net-(U$7-OSCI)") (class "Default")
      (node (ref "C35") (pin "1") (pinfunction "1_1") (pintype "passive"))
      (node (ref "U$7") (pin "6") (pinfunction "OSCI_6") (pintype "power_in"))
      (node (ref "U$8") (pin "1") (pinfunction "1_1") (pintype "passive"))
    )
    (net (code "100") (name "Net-(U$7-OSCO)") (class "Default")
      (node (ref "C34") (pin "1") (pinfunction "1_1") (pintype "passive"))
      (node (ref "U$7") (pin "7") (pinfunction "OSCO_7") (pintype "power_in"))
      (node (ref "U$8") (pin "2") (pinfunction "3_2") (pintype "passive"))
    )
    (net (code "101") (name "Net-(U$7-REFIN+{slash}OUT)") (class "Default")
      (node (ref "C31") (pin "1") (pinfunction "1_1") (pintype "passive"))
      (node (ref "U$7") (pin "23") (pinfunction "REFIN+/OUT_23") (pintype "bidirectional"))
    )
    (net (code "102") (name "Net-(U$7-V1+)") (class "Default")
      (node (ref "C28") (pin "1") (pinfunction "1_1") (pintype "passive"))
      (node (ref "R56") (pin "1") (pinfunction "1_1") (pintype "passive"))
      (node (ref "U$7") (pin "19") (pinfunction "V1+_19") (pintype "power_in"))
    )
    (net (code "103") (name "Net-(U$7-V1-)") (class "Default")
      (node (ref "C22") (pin "1") (pinfunction "1_1") (pintype "passive"))
      (node (ref "R54") (pin "2") (pinfunction "2_2") (pintype "passive"))
      (node (ref "R55") (pin "1") (pinfunction "1_1") (pintype "passive"))
      (node (ref "TP1") (pin "TP") (pinfunction "TP_TP") (pintype "input"))
      (node (ref "U$7") (pin "18") (pinfunction "V1-_18") (pintype "power_in"))
    )
    (net (code "104") (name "Net-(U$9-IN2)") (class "Default")
      (node (ref "JP5") (pin "3") (pinfunction "3_3") (pintype "passive"))
      (node (ref "R76") (pin "1") (pinfunction "1_1") (pintype "passive"))
      (node (ref "U$9") (pin "6") (pinfunction "IN2_6") (pintype "input"))
    )
    (net (code "105") (name "Net-(U$9-OUT1)") (class "Default")
      (node (ref "JP5") (pin "2") (pinfunction "2_2") (pintype "passive"))
      (node (ref "R75") (pin "1") (pinfunction "1_1") (pintype "passive"))
      (node (ref "U$9") (pin "7") (pinfunction "OUT1_7") (pintype "output"))
    )
    (net (code "106") (name "Net-(U$9-VDD2)") (class "Default")
      (node (ref "JP21") (pin "2") (pinfunction "2_2") (pintype "passive"))
      (node (ref "R80") (pin "1") (pinfunction "1_1") (pintype "passive"))
      (node (ref "U$9") (pin "8") (pinfunction "VDD2_8") (pintype "power_in"))
    )
    (net (code "107") (name "Net-(U$10-VO)") (class "Default")
      (node (ref "R68") (pin "1") (pinfunction "1_1") (pintype "passive"))
      (node (ref "U$10") (pin "2") (pinfunction "VO_2") (pintype "bidirectional"))
    )
    (net (code "108") (name "Net-(U1-ISET)") (class "Default")
      (node (ref "R1") (pin "2") (pinfunction "2_2") (pintype "passive"))
      (node (ref "U1") (pin "2") (pinfunction "ISET_2") (pintype "input"))
    )
    (net (code "109") (name "Net-(U1-TS)") (class "Default")
      (node (ref "R2") (pin "2") (pinfunction "2_2") (pintype "passive"))
      (node (ref "R3") (pin "2") (pinfunction "2_2") (pintype "passive"))
      (node (ref "U1") (pin "5") (pinfunction "TS_5") (pintype "input"))
    )
    (net (code "110") (name "Net-(U1-VTSB)") (class "Default")
      (node (ref "R2") (pin "1") (pinfunction "1_1") (pintype "passive"))
      (node (ref "U1") (pin "4") (pinfunction "VTSB_4") (pintype "output"))
    )
    (net (code "111") (name "Net-(U1-~{CHG})") (class "Default")
      (node (ref "LED1") (pin "C") (pinfunction "C_C") (pintype "passive"))
      (node (ref "U1") (pin "8") (pinfunction "~{CHG}_8") (pintype "output"))
    )
    (net (code "112") (name "OUT1") (class "Default")
      (node (ref "JP25") (pin "1") (pinfunction "1_1") (pintype "passive"))
      (node (ref "Q5") (pin "2") (pinfunction "D_2") (pintype "passive"))
      (node (ref "Q5") (pin "4") (pinfunction "D_4") (pintype "passive"))
    )
    (net (code "113") (name "OUT2") (class "Default")
      (node (ref "JP25") (pin "2") (pinfunction "2_2") (pintype "passive"))
      (node (ref "Q1") (pin "2") (pinfunction "D_2") (pintype "passive"))
      (node (ref "Q1") (pin "4") (pinfunction "D_4") (pintype "passive"))
    )
    (net (code "114") (name "P1.0") (class "Default")
      (node (ref "JP10") (pin "5") (pinfunction "5_5") (pintype "passive"))
      (node (ref "MSP430F5529") (pin "21") (pinfunction "21_21") (pintype "bidirectional"))
    )
    (net (code "115") (name "P1.1") (class "Default")
      (node (ref "JP10") (pin "4") (pinfunction "4_4") (pintype "passive"))
      (node (ref "MSP430F5529") (pin "22") (pinfunction "22_22") (pintype "bidirectional"))
    )
    (net (code "116") (name "P1.2") (class "Default")
      (node (ref "JP10") (pin "3") (pinfunction "3_3") (pintype "passive"))
      (node (ref "JP2") (pin "1") (pinfunction "1_1") (pintype "passive"))
      (node (ref "MSP430F5529") (pin "23") (pinfunction "23_23") (pintype "bidirectional"))
    )
    (net (code "117") (name "P1.3") (class "Default")
      (node (ref "JP10") (pin "2") (pinfunction "2_2") (pintype "passive"))
      (node (ref "JP3") (pin "1") (pinfunction "1_1") (pintype "passive"))
      (node (ref "MSP430F5529") (pin "24") (pinfunction "24_24") (pintype "bidirectional"))
    )
    (net (code "118") (name "P1.4") (class "Default")
      (node (ref "JP4") (pin "5") (pinfunction "5_5") (pintype "passive"))
      (node (ref "MSP430F5529") (pin "25") (pinfunction "25_25") (pintype "bidirectional"))
    )
    (net (code "119") (name "P1.5") (class "Default")
      (node (ref "JP4") (pin "4") (pinfunction "4_4") (pintype "passive"))
      (node (ref "MSP430F5529") (pin "26") (pinfunction "26_26") (pintype "bidirectional"))
    )
    (net (code "120") (name "P1.6") (class "Default")
      (node (ref "MSP430F5529") (pin "27") (pinfunction "27_27") (pintype "bidirectional"))
      (node (ref "NRF24L01") (pin "8") (pinfunction "IRQ_8") (pintype "bidirectional"))
    )
    (net (code "121") (name "P1.7") (class "Default")
      (node (ref "JP4") (pin "3") (pinfunction "3_3") (pintype "passive"))
      (node (ref "MSP430F5529") (pin "28") (pinfunction "28_28") (pintype "bidirectional"))
    )
    (net (code "122") (name "P2.0") (class "Default")
      (node (ref "JP4") (pin "2") (pinfunction "2_2") (pintype "passive"))
      (node (ref "MSP430F5529") (pin "29") (pinfunction "29_29") (pintype "bidirectional"))
    )
    (net (code "123") (name "P2.1") (class "Default")
      (node (ref "MSP430F5529") (pin "30") (pinfunction "30_30") (pintype "bidirectional"))
    )
    (net (code "124") (name "P2.2") (class "Default")
      (node (ref "MSP430F5529") (pin "31") (pinfunction "31_31") (pintype "bidirectional"))
      (node (ref "NRF24L01") (pin "4") (pinfunction "CSN_4") (pintype "bidirectional"))
    )
    (net (code "125") (name "P2.3") (class "Default")
      (node (ref "MSP430F5529") (pin "32") (pinfunction "32_32") (pintype "bidirectional"))
    )
    (net (code "126") (name "P2.4") (class "Default")
      (node (ref "MSP430F5529") (pin "33") (pinfunction "33_33") (pintype "bidirectional"))
    )
    (net (code "127") (name "P2.5") (class "Default")
      (node (ref "MSP430F5529") (pin "34") (pinfunction "34_34") (pintype "bidirectional"))
      (node (ref "NRF24L01") (pin "3") (pinfunction "CE_3") (pintype "bidirectional"))
    )
    (net (code "128") (name "P2.6") (class "Default")
      (node (ref "MSP430F5529") (pin "35") (pinfunction "35_35") (pintype "bidirectional"))
    )
    (net (code "129") (name "P2.7") (class "Default")
      (node (ref "JP8") (pin "4") (pinfunction "4_4") (pintype "passive"))
      (node (ref "MSP430F5529") (pin "36") (pinfunction "36_36") (pintype "bidirectional"))
      (node (ref "R77") (pin "2") (pinfunction "2_2") (pintype "passive"))
    )
    (net (code "130") (name "P2.7_H") (class "Default")
      (node (ref "JP5") (pin "1") (pinfunction "1_1") (pintype "passive"))
      (node (ref "OK4") (pin "1") (pinfunction "A_1") (pintype "passive"))
      (node (ref "R77") (pin "1") (pinfunction "1_1") (pintype "passive"))
    )
    (net (code "131") (name "P3.0") (class "Default")
      (node (ref "MSP430F5529") (pin "37") (pinfunction "37_37") (pintype "bidirectional"))
      (node (ref "NRF24L01") (pin "6") (pinfunction "MOSI_6") (pintype "bidirectional"))
    )
    (net (code "132") (name "P3.1") (class "Default")
      (node (ref "MSP430F5529") (pin "38") (pinfunction "38_38") (pintype "bidirectional"))
      (node (ref "NRF24L01") (pin "7") (pinfunction "MISO_7") (pintype "bidirectional"))
    )
    (net (code "133") (name "P3.2") (class "Default")
      (node (ref "MSP430F5529") (pin "39") (pinfunction "39_39") (pintype "bidirectional"))
      (node (ref "NRF24L01") (pin "5") (pinfunction "SCK_5") (pintype "bidirectional"))
    )
    (net (code "134") (name "P3.3_UCA0TX") (class "Default")
      (node (ref "JP8") (pin "2") (pinfunction "2_2") (pintype "passive"))
      (node (ref "MSP430F5529") (pin "40") (pinfunction "40_40") (pintype "bidirectional"))
      (node (ref "R76") (pin "2") (pinfunction "2_2") (pintype "passive"))
    )
    (net (code "135") (name "P3.4_UCA0RX") (class "Default")
      (node (ref "JP8") (pin "3") (pinfunction "3_3") (pintype "passive"))
      (node (ref "MSP430F5529") (pin "41") (pinfunction "41_41") (pintype "bidirectional"))
      (node (ref "R75") (pin "2") (pinfunction "2_2") (pintype "passive"))
    )
    (net (code "136") (name "P3.5") (class "Default")
      (node (ref "MSP430F5529") (pin "42") (pinfunction "42_42") (pintype "bidirectional"))
      (node (ref "R90") (pin "2") (pinfunction "2_2") (pintype "passive"))
    )
    (net (code "137") (name "P3.6") (class "Default")
      (node (ref "MSP430F5529") (pin "43") (pinfunction "43_43") (pintype "bidirectional"))
    )
    (net (code "138") (name "P3.7") (class "Default")
      (node (ref "MSP430F5529") (pin "44") (pinfunction "44_44") (pintype "bidirectional"))
      (node (ref "R88") (pin "2") (pinfunction "2_2") (pintype "passive"))
    )
    (net (code "139") (name "P4.0") (class "Default")
      (node (ref "MSP430F5529") (pin "45") (pinfunction "45_45") (pintype "bidirectional"))
    )
    (net (code "140") (name "P4.1") (class "Default")
      (node (ref "MSP430F5529") (pin "46") (pinfunction "46_46") (pintype "bidirectional"))
      (node (ref "R25") (pin "1") (pinfunction "1_1") (pintype "passive"))
      (node (ref "R33") (pin "1") (pinfunction "1_1") (pintype "passive"))
      (node (ref "R34") (pin "1") (pinfunction "1_1") (pintype "passive"))
      (node (ref "R8") (pin "1") (pinfunction "1_1") (pintype "passive"))
      (node (ref "R83") (pin "2") (pinfunction "2_2") (pintype "passive"))
    )
    (net (code "141") (name "P4.2") (class "Default")
      (node (ref "MSP430F5529") (pin "47") (pinfunction "47_47") (pintype "bidirectional"))
      (node (ref "R24") (pin "1") (pinfunction "1_1") (pintype "passive"))
      (node (ref "R35") (pin "1") (pinfunction "1_1") (pintype "passive"))
      (node (ref "R36") (pin "1") (pinfunction "1_1") (pintype "passive"))
      (node (ref "R84") (pin "2") (pinfunction "2_2") (pintype "passive"))
      (node (ref "R9") (pin "1") (pinfunction "1_1") (pintype "passive"))
    )
    (net (code "142") (name "P4.3") (class "Default")
      (node (ref "MSP430F5529") (pin "48") (pinfunction "48_48") (pintype "bidirectional"))
    )
    (net (code "143") (name "P4.4{slash}UCA1TXD") (class "Default")
      (node (ref "JP1") (pin "3") (pinfunction "3_3") (pintype "passive"))
      (node (ref "MSP430F5529") (pin "51") (pinfunction "51_51") (pintype "bidirectional"))
      (node (ref "R22") (pin "1") (pinfunction "1_1") (pintype "passive"))
    )
    (net (code "144") (name "P4.5{slash}UCA1RXD") (class "Default")
      (node (ref "JP1") (pin "5") (pinfunction "5_5") (pintype "passive"))
      (node (ref "MSP430F5529") (pin "52") (pinfunction "52_52") (pintype "bidirectional"))
      (node (ref "R23") (pin "1") (pinfunction "1_1") (pintype "passive"))
    )
    (net (code "145") (name "P4.6") (class "Default")
      (node (ref "MSP430F5529") (pin "53") (pinfunction "53_53") (pintype "bidirectional"))
      (node (ref "R43") (pin "1") (pinfunction "1_1") (pintype "passive"))
    )
    (net (code "146") (name "P4.7") (class "Default")
      (node (ref "MSP430F5529") (pin "54") (pinfunction "54_54") (pintype "bidirectional"))
      (node (ref "R42") (pin "1") (pinfunction "1_1") (pintype "passive"))
    )
    (net (code "147") (name "P5.6") (class "Default")
      (node (ref "MSP430F5529") (pin "55") (pinfunction "55_55") (pintype "bidirectional"))
      (node (ref "R41") (pin "1") (pinfunction "1_1") (pintype "passive"))
    )
    (net (code "148") (name "P6.0") (class "Default")
      (node (ref "JP18") (pin "5") (pinfunction "5_5") (pintype "passive"))
      (node (ref "MSP430F5529") (pin "77") (pinfunction "77_77") (pintype "bidirectional"))
    )
    (net (code "149") (name "P6.1") (class "Default")
      (node (ref "JP18") (pin "4") (pinfunction "4_4") (pintype "passive"))
      (node (ref "MSP430F5529") (pin "78") (pinfunction "78_78") (pintype "bidirectional"))
    )
    (net (code "150") (name "P6.2") (class "Default")
      (node (ref "JP18") (pin "3") (pinfunction "3_3") (pintype "passive"))
      (node (ref "MSP430F5529") (pin "79") (pinfunction "79_79") (pintype "bidirectional"))
    )
    (net (code "151") (name "P6.3") (class "Default")
      (node (ref "JP18") (pin "2") (pinfunction "2_2") (pintype "passive"))
      (node (ref "MSP430F5529") (pin "80") (pinfunction "80_80") (pintype "bidirectional"))
    )
    (net (code "152") (name "P6.4") (class "Default")
      (node (ref "MSP430F5529") (pin "1") (pinfunction "1_1") (pintype "bidirectional"))
      (node (ref "U$5") (pin "3") (pinfunction "AIN_3") (pintype "input"))
    )
    (net (code "153") (name "P6.4_5V") (class "Default")
      (node (ref "JP9") (pin "5") (pinfunction "5_5") (pintype "passive"))
      (node (ref "U$5") (pin "2") (pinfunction "AOUT_2") (pintype "input"))
    )
    (net (code "154") (name "P6.5") (class "Default")
      (node (ref "MSP430F5529") (pin "2") (pinfunction "2_2") (pintype "bidirectional"))
      (node (ref "U$5") (pin "5") (pinfunction "BIN_5") (pintype "input"))
    )
    (net (code "155") (name "P6.5_5V") (class "Default")
      (node (ref "JP9") (pin "4") (pinfunction "4_4") (pintype "passive"))
      (node (ref "U$5") (pin "4") (pinfunction "BOUT_4") (pintype "input"))
    )
    (net (code "156") (name "P6.6") (class "Default")
      (node (ref "MSP430F5529") (pin "3") (pinfunction "3_3") (pintype "bidirectional"))
      (node (ref "U$5") (pin "7") (pinfunction "CIN_7") (pintype "tri_state"))
    )
    (net (code "157") (name "P6.6_5V") (class "Default")
      (node (ref "JP9") (pin "3") (pinfunction "3_3") (pintype "passive"))
      (node (ref "U$5") (pin "6") (pinfunction "COUT_6") (pintype "tri_state"))
    )
    (net (code "158") (name "P6.7") (class "Default")
      (node (ref "MSP430F5529") (pin "4") (pinfunction "4_4") (pintype "bidirectional"))
      (node (ref "U$5") (pin "14") (pinfunction "FIN_14") (pintype "input"))
    )
    (net (code "159") (name "P6.7_5V") (class "Default")
      (node (ref "JP9") (pin "2") (pinfunction "2_2") (pintype "passive"))
      (node (ref "U$5") (pin "15") (pinfunction "FOUT_15") (pintype "input"))
    )
    (net (code "160") (name "P7.0") (class "Default")
      (node (ref "MSP430F5529") (pin "5") (pinfunction "5_5") (pintype "bidirectional"))
      (node (ref "R40") (pin "1") (pinfunction "1_1") (pintype "passive"))
    )
    (net (code "161") (name "P7.1") (class "Default")
      (node (ref "MSP430F5529") (pin "6") (pinfunction "6_6") (pintype "bidirectional"))
      (node (ref "R52") (pin "1") (pinfunction "1_1") (pintype "passive"))
    )
    (net (code "162") (name "P7.2") (class "Default")
      (node (ref "MSP430F5529") (pin "7") (pinfunction "7_7") (pintype "bidirectional"))
      (node (ref "R47") (pin "1") (pinfunction "1_1") (pintype "passive"))
    )
    (net (code "163") (name "P7.3") (class "Default")
      (node (ref "MSP430F5529") (pin "8") (pinfunction "8_8") (pintype "bidirectional"))
      (node (ref "R48") (pin "1") (pinfunction "1_1") (pintype "passive"))
    )
    (net (code "164") (name "P7.4") (class "Default")
      (node (ref "JP12") (pin "2") (pinfunction "2_2") (pintype "passive"))
      (node (ref "MSP430F5529") (pin "57") (pinfunction "57_57") (pintype "bidirectional"))
    )
    (net (code "165") (name "P7.5") (class "Default")
      (node (ref "JP12") (pin "3") (pinfunction "3_3") (pintype "passive"))
      (node (ref "MSP430F5529") (pin "58") (pinfunction "58_58") (pintype "bidirectional"))
    )
    (net (code "166") (name "P7.6") (class "Default")
      (node (ref "JP12") (pin "4") (pinfunction "4_4") (pintype "passive"))
      (node (ref "MSP430F5529") (pin "59") (pinfunction "59_59") (pintype "bidirectional"))
    )
    (net (code "167") (name "P7.7") (class "Default")
      (node (ref "JP12") (pin "5") (pinfunction "5_5") (pintype "passive"))
      (node (ref "MSP430F5529") (pin "60") (pinfunction "60_60") (pintype "bidirectional"))
    )
    (net (code "168") (name "P8.1") (class "Default")
      (node (ref "MSP430F5529") (pin "16") (pinfunction "16_16") (pintype "bidirectional"))
    )
    (net (code "169") (name "P8.2") (class "Default")
      (node (ref "MSP430F5529") (pin "17") (pinfunction "17_17") (pintype "bidirectional"))
    )
    (net (code "170") (name "PE") (class "Default")
      (node (ref "X2") (pin "2") (pinfunction "1_2") (pintype "passive"))
      (node (ref "X3") (pin "2") (pinfunction "1_2") (pintype "passive"))
    )
    (net (code "171") (name "RELAY") (class "Default")
      (node (ref "IC3") (pin "1") (pinfunction "VIN_1") (pintype "passive"))
      (node (ref "OK4") (pin "3") (pinfunction "EMIT_3") (pintype "passive"))
    )
    (net (code "172") (name "RST{slash}SBWTDIO") (class "Default")
      (node (ref "C17") (pin "1") (pinfunction "1_1") (pintype "passive"))
      (node (ref "JP1") (pin "4") (pinfunction "4_4") (pintype "passive"))
      (node (ref "MSP430F5529") (pin "76") (pinfunction "76_76") (pintype "bidirectional"))
      (node (ref "R27") (pin "1") (pinfunction "1_1") (pintype "passive"))
      (node (ref "S3") (pin "2") (pinfunction "S_2") (pintype "passive"))
    )
    (net (code "173") (name "RXD_2102") (class "Default")
      (node (ref "IC2") (pin "25") (pinfunction "RXD_25") (pintype "input"))
      (node (ref "R22") (pin "2") (pinfunction "2_2") (pintype "passive"))
    )
    (net (code "174") (name "SCL_BQ27510") (class "Default")
      (node (ref "BQ27510") (pin "11") (pinfunction "SCL_11") (pintype "input"))
      (node (ref "R24") (pin "2") (pinfunction "2_2") (pintype "passive"))
    )
    (net (code "175") (name "SCL_EXT1") (class "Default")
      (node (ref "JP6") (pin "2") (pinfunction "2_2") (pintype "passive"))
      (node (ref "R35") (pin "2") (pinfunction "2_2") (pintype "passive"))
    )
    (net (code "176") (name "SCL_EXT2") (class "Default")
      (node (ref "JP7") (pin "2") (pinfunction "2_2") (pintype "passive"))
      (node (ref "R36") (pin "2") (pinfunction "2_2") (pintype "passive"))
    )
    (net (code "177") (name "SCL_MEM") (class "Default")
      (node (ref "R84") (pin "1") (pinfunction "1_1") (pintype "passive"))
      (node (ref "U5") (pin "6") (pinfunction "SCL_6") (pintype "power_in"))
    )
    (net (code "178") (name "SDA_BQ27510") (class "Default")
      (node (ref "BQ27510") (pin "10") (pinfunction "SDA_10") (pintype "bidirectional"))
      (node (ref "R25") (pin "2") (pinfunction "2_2") (pintype "passive"))
    )
    (net (code "179") (name "SDA_EXT1") (class "Default")
      (node (ref "JP6") (pin "1") (pinfunction "1_1") (pintype "passive"))
      (node (ref "R33") (pin "2") (pinfunction "2_2") (pintype "passive"))
    )
    (net (code "180") (name "SDA_EXT2") (class "Default")
      (node (ref "JP7") (pin "1") (pinfunction "1_1") (pintype "passive"))
      (node (ref "R34") (pin "2") (pinfunction "2_2") (pintype "passive"))
    )
    (net (code "181") (name "SDA_MEM") (class "Default")
      (node (ref "R83") (pin "1") (pinfunction "1_1") (pintype "passive"))
      (node (ref "U5") (pin "5") (pinfunction "SDA_5") (pintype "power_in"))
    )
    (net (code "182") (name "TARGET_DM") (class "Default")
      (node (ref "C24") (pin "1") (pinfunction "1_1") (pintype "passive"))
      (node (ref "MSP430F5529") (pin "64") (pinfunction "64_64") (pintype "bidirectional"))
      (node (ref "R31") (pin "2") (pinfunction "2_2") (pintype "passive"))
    )
    (net (code "183") (name "TARGET_DP") (class "Default")
      (node (ref "C23") (pin "1") (pinfunction "1_1") (pintype "passive"))
      (node (ref "MSP430F5529") (pin "62") (pinfunction "62_62") (pintype "bidirectional"))
      (node (ref "R15") (pin "2") (pinfunction "2_2") (pintype "passive"))
      (node (ref "R32") (pin "2") (pinfunction "2_2") (pintype "passive"))
    )
    (net (code "184") (name "TARGET_PUR") (class "Default")
      (node (ref "MSP430F5529") (pin "63") (pinfunction "63_63") (pintype "bidirectional"))
      (node (ref "R14") (pin "2") (pinfunction "2_2") (pintype "passive"))
      (node (ref "R15") (pin "1") (pinfunction "1_1") (pintype "passive"))
      (node (ref "R16") (pin "2") (pinfunction "2_2") (pintype "passive"))
    )
    (net (code "185") (name "TEST{slash}SBWTCK") (class "Default")
      (node (ref "JP1") (pin "6") (pinfunction "6_6") (pintype "passive"))
      (node (ref "MSP430F5529") (pin "71") (pinfunction "71_71") (pintype "input"))
    )
    (net (code "186") (name "TXD_2102") (class "Default")
      (node (ref "IC2") (pin "26") (pinfunction "TXD_26") (pintype "output"))
      (node (ref "R23") (pin "2") (pinfunction "2_2") (pintype "passive"))
    )
    (net (code "187") (name "UART_RX_HIGH") (class "Default")
      (node (ref "U$7") (pin "4") (pinfunction "UART_RX_4") (pintype "bidirectional"))
      (node (ref "U$9") (pin "3") (pinfunction "OUT2_3") (pintype "output"))
    )
    (net (code "188") (name "UART_TX_HIGH") (class "Default")
      (node (ref "U$7") (pin "12") (pinfunction "UART_TX_12") (pintype "power_in"))
      (node (ref "U$9") (pin "2") (pinfunction "IN1_2") (pintype "input"))
    )
    (net (code "189") (name "V+") (class "Default")
      (node (ref "CN1") (pin "PWR1") (pinfunction "PWR_PWR1") (pintype "power_in"))
      (node (ref "D7") (pin "1") (pinfunction "A_1") (pintype "passive"))
      (node (ref "JP25") (pin "3") (pinfunction "3_3") (pintype "passive"))
      (node (ref "R89") (pin "1") (pinfunction "1_1") (pintype "passive"))
    )
    (net (code "190") (name "VBAT+") (class "Default")
      (node (ref "BQ27510") (pin "3") (pinfunction "REGIN_3") (pintype "input"))
      (node (ref "BQ27510") (pin "4") (pinfunction "BAT_4") (pintype "input"))
      (node (ref "C10") (pin "1") (pinfunction "1_1") (pintype "passive"))
      (node (ref "C3") (pin "1") (pinfunction "1_1") (pintype "passive"))
      (node (ref "C8") (pin "1") (pinfunction "1_1") (pintype "passive"))
      (node (ref "R13") (pin "1") (pinfunction "1_1") (pintype "passive"))
      (node (ref "R19") (pin "1") (pinfunction "1_1") (pintype "passive"))
      (node (ref "R6") (pin "2") (pinfunction "2_2") (pintype "passive"))
      (node (ref "R7") (pin "2") (pinfunction "2_2") (pintype "passive"))
      (node (ref "TPS63001") (pin "5") (pinfunction "VIN_5") (pintype "input"))
      (node (ref "TPS63001") (pin "8") (pinfunction "VINA_8") (pintype "input"))
      (node (ref "TPS63002") (pin "5") (pinfunction "VIN_5") (pintype "input"))
      (node (ref "TPS63002") (pin "8") (pinfunction "VINA_8") (pintype "input"))
      (node (ref "U$1") (pin "P$1") (pinfunction "+_P$1") (pintype "passive"))
      (node (ref "U1") (pin "10") (pinfunction "BAT_10") (pintype "bidirectional"))
      (node (ref "X4") (pin "2") (pinfunction "1_2") (pintype "passive"))
    )
    (net (code "191") (name "VBAT-") (class "Default")
      (node (ref "R11") (pin "2") (pinfunction "2_2") (pintype "passive"))
      (node (ref "R12") (pin "2") (pinfunction "2_2") (pintype "passive"))
      (node (ref "U$1") (pin "P$2") (pinfunction "-_P$2") (pintype "passive"))
      (node (ref "X4") (pin "1") (pinfunction "1_1") (pintype "passive"))
    )
    (net (code "192") (name "VBUS") (class "Default")
      (node (ref "C1") (pin "1") (pinfunction "1_1") (pintype "passive"))
      (node (ref "C12") (pin "1") (pinfunction "1_1") (pintype "passive"))
      (node (ref "C13") (pin "1") (pinfunction "1_1") (pintype "passive"))
      (node (ref "C403") (pin "+") (pinfunction "+_+") (pintype "passive"))
      (node (ref "D1") (pin "C") (pinfunction "A_C") (pintype "passive"))
      (node (ref "D7") (pin "3") (pinfunction "C_3") (pintype "passive"))
      (node (ref "D8") (pin "3") (pinfunction "C_3") (pintype "passive"))
      (node (ref "IC2") (pin "7") (pinfunction "REGIN_7") (pintype "passive"))
      (node (ref "IC2") (pin "8") (pinfunction "VBUS_8") (pintype "input"))
      (node (ref "JP13") (pin "2") (pinfunction "2_2") (pintype "passive"))
      (node (ref "R86") (pin "2") (pinfunction "2_2") (pintype "passive"))
      (node (ref "R89") (pin "2") (pinfunction "2_2") (pintype "passive"))
      (node (ref "U1") (pin "1") (pinfunction "VBUS_1") (pintype "bidirectional"))
      (node (ref "U404") (pin "1") (pinfunction "VCC_1") (pintype "power_in"))
    )
    (net (code "193") (name "VDD") (class "Default")
      (node (ref "C14") (pin "1") (pinfunction "1_1") (pintype "passive"))
      (node (ref "C19") (pin "2") (pinfunction "2_2") (pintype "passive"))
      (node (ref "C30") (pin "+") (pinfunction "+_+") (pintype "passive"))
      (node (ref "C40") (pin "2") (pinfunction "2_2") (pintype "passive"))
      (node (ref "C50") (pin "1") (pinfunction "1_1") (pintype "passive"))
      (node (ref "D2") (pin "C") (pinfunction "A_C") (pintype "passive"))
      (node (ref "JP1") (pin "2") (pinfunction "2_2") (pintype "passive"))
      (node (ref "JP11") (pin "1") (pinfunction "1_1") (pintype "passive"))
      (node (ref "JP22") (pin "2") (pinfunction "2_2") (pintype "passive"))
      (node (ref "JP24") (pin "1") (pinfunction "1_1") (pintype "passive"))
      (node (ref "LED3") (pin "A") (pinfunction "A_A") (pintype "passive"))
      (node (ref "LED4") (pin "A") (pinfunction "A_A") (pintype "passive"))
      (node (ref "LED5") (pin "A") (pinfunction "A_A") (pintype "passive"))
      (node (ref "MSP430F5529") (pin "18") (pinfunction "18_18") (pintype "power_in"))
      (node (ref "MSP430F5529") (pin "50") (pinfunction "50_50") (pintype "power_in"))
      (node (ref "NRF24L01") (pin "2") (pinfunction "+3.3V_2") (pintype "power_in"))
      (node (ref "R27") (pin "2") (pinfunction "2_2") (pintype "passive"))
      (node (ref "R28") (pin "2") (pinfunction "2_2") (pintype "passive"))
      (node (ref "R38") (pin "1") (pinfunction "1_1") (pintype "passive"))
      (node (ref "R4") (pin "2") (pinfunction "2_2") (pintype "passive"))
      (node (ref "R8") (pin "2") (pinfunction "2_2") (pintype "passive"))
      (node (ref "R80") (pin "2") (pinfunction "2_2") (pintype "passive"))
      (node (ref "R82") (pin "2") (pinfunction "2_2") (pintype "passive"))
      (node (ref "R9") (pin "2") (pinfunction "2_2") (pintype "passive"))
      (node (ref "S5") (pin "1") (pinfunction "P_1") (pintype "passive"))
      (node (ref "U$5") (pin "1") (pinfunction "VCC_1") (pintype "input"))
      (node (ref "U5") (pin "8") (pinfunction "VCC_8") (pintype "input"))
    )
    (net (code "194") (name "VEXT") (class "Default")
      (node (ref "C21") (pin "1") (pinfunction "1_1") (pintype "passive"))
      (node (ref "JP13") (pin "1") (pinfunction "1_1") (pintype "passive"))
      (node (ref "R26") (pin "1") (pinfunction "1_1") (pintype "passive"))
      (node (ref "TPS63061") (pin "5") (pinfunction "VIN_5") (pintype "input"))
      (node (ref "TPS63061") (pin "8") (pinfunction "VINA_8") (pintype "input"))
    )
    (net (code "195") (name "VOLTAGE_IN") (class "Default")
      (node (ref "L3") (pin "2") (pinfunction "2_2") (pintype "passive"))
      (node (ref "R53") (pin "1") (pinfunction "1_1") (pintype "passive"))
      (node (ref "R65") (pin "1") (pinfunction "1_1") (pintype "passive"))
      (node (ref "TP3") (pin "TP") (pinfunction "TP_TP") (pintype "input"))
    )
    (net (code "196") (name "unconnected-(IC2-CTS-Pad23)") (class "Default")
      (node (ref "IC2") (pin "23") (pinfunction "CTS_23") (pintype "input"))
    )
    (net (code "197") (name "unconnected-(IC2-DCD-Pad1)") (class "Default")
      (node (ref "IC2") (pin "1") (pinfunction "DCD_1") (pintype "input"))
    )
    (net (code "198") (name "unconnected-(IC2-DSR-Pad27)") (class "Default")
      (node (ref "IC2") (pin "27") (pinfunction "DSR_27") (pintype "input"))
    )
    (net (code "199") (name "unconnected-(IC2-DTR-Pad28)") (class "Default")
      (node (ref "IC2") (pin "28") (pinfunction "DTR_28") (pintype "output"))
    )
    (net (code "200") (name "unconnected-(IC2-RI-Pad2)") (class "Default")
      (node (ref "IC2") (pin "2") (pinfunction "RI_2") (pintype "input"))
    )
    (net (code "201") (name "unconnected-(IC2-RTS-Pad24)") (class "Default")
      (node (ref "IC2") (pin "24") (pinfunction "RTS_24") (pintype "output"))
    )
    (net (code "202") (name "unconnected-(IC2-SUSPEND-Pad12)") (class "Default")
      (node (ref "IC2") (pin "12") (pinfunction "SUSPEND_12") (pintype "output"))
    )
    (net (code "203") (name "unconnected-(IC2-~{RST}-Pad9)") (class "Default")
      (node (ref "IC2") (pin "9") (pinfunction "~{RST}_9") (pintype "bidirectional"))
    )
    (net (code "204") (name "unconnected-(IC2-~{SUSPEND}-Pad11)") (class "Default")
      (node (ref "IC2") (pin "11") (pinfunction "~{SUSPEND}_11") (pintype "output"))
    )
    (net (code "205") (name "unconnected-(J401-PadNC)") (class "Default")
      (node (ref "J401") (pin "NC") (pinfunction "NC_NC") (pintype "input"))
    )
    (net (code "206") (name "unconnected-(J401-PadSHIELD2)") (class "Default")
      (node (ref "J401") (pin "SHIELD2") (pinfunction "SHIELD2_SHIELD2") (pintype "bidirectional"))
    )
    (net (code "207") (name "unconnected-(J401-PadSHIELD3)") (class "Default")
      (node (ref "J401") (pin "SHIELD3") (pinfunction "SHIELD3_SHIELD3") (pintype "bidirectional"))
    )
    (net (code "208") (name "unconnected-(J401-PadSHIELD4)") (class "Default")
      (node (ref "J401") (pin "SHIELD4") (pinfunction "SHIELD4_SHIELD4") (pintype "bidirectional"))
    )
    (net (code "209") (name "unconnected-(J401-PadSHIELD5)") (class "Default")
      (node (ref "J401") (pin "SHIELD5") (pinfunction "SHIELD5_SHIELD5") (pintype "bidirectional"))
    )
    (net (code "210") (name "unconnected-(J401-PadSHIELD6)") (class "Default")
      (node (ref "J401") (pin "SHIELD6") (pinfunction "SHIELD6_SHIELD6") (pintype "bidirectional"))
    )
    (net (code "211") (name "unconnected-(K2A-O-Pad2)") (class "Default")
      (node (ref "K2") (pin "2") (pinfunction "O_2") (pintype "passive"))
    )
    (net (code "212") (name "unconnected-(K2B-O-Pad7)") (class "Default")
      (node (ref "K2") (pin "7") (pinfunction "O_7") (pintype "passive"))
    )
    (net (code "213") (name "unconnected-(MSP430F5529-Pad9)") (class "Default")
      (node (ref "MSP430F5529") (pin "9") (pinfunction "9_9") (pintype "bidirectional"))
    )
    (net (code "214") (name "unconnected-(MSP430F5529-Pad10)") (class "Default")
      (node (ref "MSP430F5529") (pin "10") (pinfunction "10_10") (pintype "bidirectional"))
    )
    (net (code "215") (name "unconnected-(MSP430F5529-Pad15)") (class "Default")
      (node (ref "MSP430F5529") (pin "15") (pinfunction "15_15") (pintype "bidirectional"))
    )
    (net (code "216") (name "unconnected-(MSP430F5529-Pad56)") (class "Default")
      (node (ref "MSP430F5529") (pin "56") (pinfunction "56_56") (pintype "bidirectional"))
    )
    (net (code "217") (name "unconnected-(MSP430F5529-Pad72)") (class "Default")
      (node (ref "MSP430F5529") (pin "72") (pinfunction "72_72") (pintype "bidirectional"))
    )
    (net (code "218") (name "unconnected-(MSP430F5529-Pad73)") (class "Default")
      (node (ref "MSP430F5529") (pin "73") (pinfunction "73_73") (pintype "bidirectional"))
    )
    (net (code "219") (name "unconnected-(MSP430F5529-Pad74)") (class "Default")
      (node (ref "MSP430F5529") (pin "74") (pinfunction "74_74") (pintype "bidirectional"))
    )
    (net (code "220") (name "unconnected-(MSP430F5529-Pad75)") (class "Default")
      (node (ref "MSP430F5529") (pin "75") (pinfunction "75_75") (pintype "bidirectional"))
    )
    (net (code "221") (name "unconnected-(U$5-DIN-Pad9)") (class "Default")
      (node (ref "U$5") (pin "9") (pinfunction "DIN_9") (pintype "input"))
    )
    (net (code "222") (name "unconnected-(U$5-DOUT-Pad10)") (class "Default")
      (node (ref "U$5") (pin "10") (pinfunction "DOUT_10") (pintype "input"))
    )
    (net (code "223") (name "unconnected-(U$5-EIN-Pad11)") (class "Default")
      (node (ref "U$5") (pin "11") (pinfunction "EIN_11") (pintype "input"))
    )
    (net (code "224") (name "unconnected-(U$5-EOUT-Pad12)") (class "Default")
      (node (ref "U$5") (pin "12") (pinfunction "EOUT_12") (pintype "input"))
    )
    (net (code "225") (name "unconnected-(U1-EP-Pad11)") (class "Default")
      (node (ref "U1") (pin "11") (pinfunction "EP_11") (pintype "passive"))
    )
    (net (code "226") (name "unconnected-(U1-VDPM-Pad9)") (class "Default")
      (node (ref "U1") (pin "9") (pinfunction "VDPM_9") (pintype "input"))
    )
    (net (code "227") (name "unconnected-(U404-NC-Pad2)") (class "Default")
      (node (ref "U404") (pin "2") (pinfunction "NC_2") (pintype "no_connect"))
    )
    (net (code "228") (name "~{BAT_LOW}") (class "Default")
      (node (ref "BQ27510") (pin "12") (pinfunction "GPOUT_12") (pintype "output"))
      (node (ref "LED2") (pin "C") (pinfunction "C_C") (pintype "passive"))
      (node (ref "R6") (pin "1") (pinfunction "1_1") (pintype "passive"))
      (node (ref "TPS63001") (pin "6") (pinfunction "EN_6") (pintype "input"))
      (node (ref "TPS63002") (pin "6") (pinfunction "EN_6") (pintype "input"))
    )
    (net (code "229") (name "~{DR}") (class "Default")
      (node (ref "U$7") (pin "28") (pinfunction "~{DR}_28") (pintype "power_in"))
    )
    (net (code "230") (name "~{EN}") (class "Default")
      (node (ref "R5") (pin "1") (pinfunction "1_1") (pintype "passive"))
      (node (ref "U1") (pin "7") (pinfunction "~{EN}_7") (pintype "input"))
    )
    (net (code "231") (name "~{PG}") (class "Default")
      (node (ref "R5") (pin "2") (pinfunction "2_2") (pintype "passive"))
      (node (ref "U1") (pin "6") (pinfunction "~{PG}_6") (pintype "output"))
    )
  )
)
